# 2.net
KiCad netlist of a schematic drawn in Altium Designer
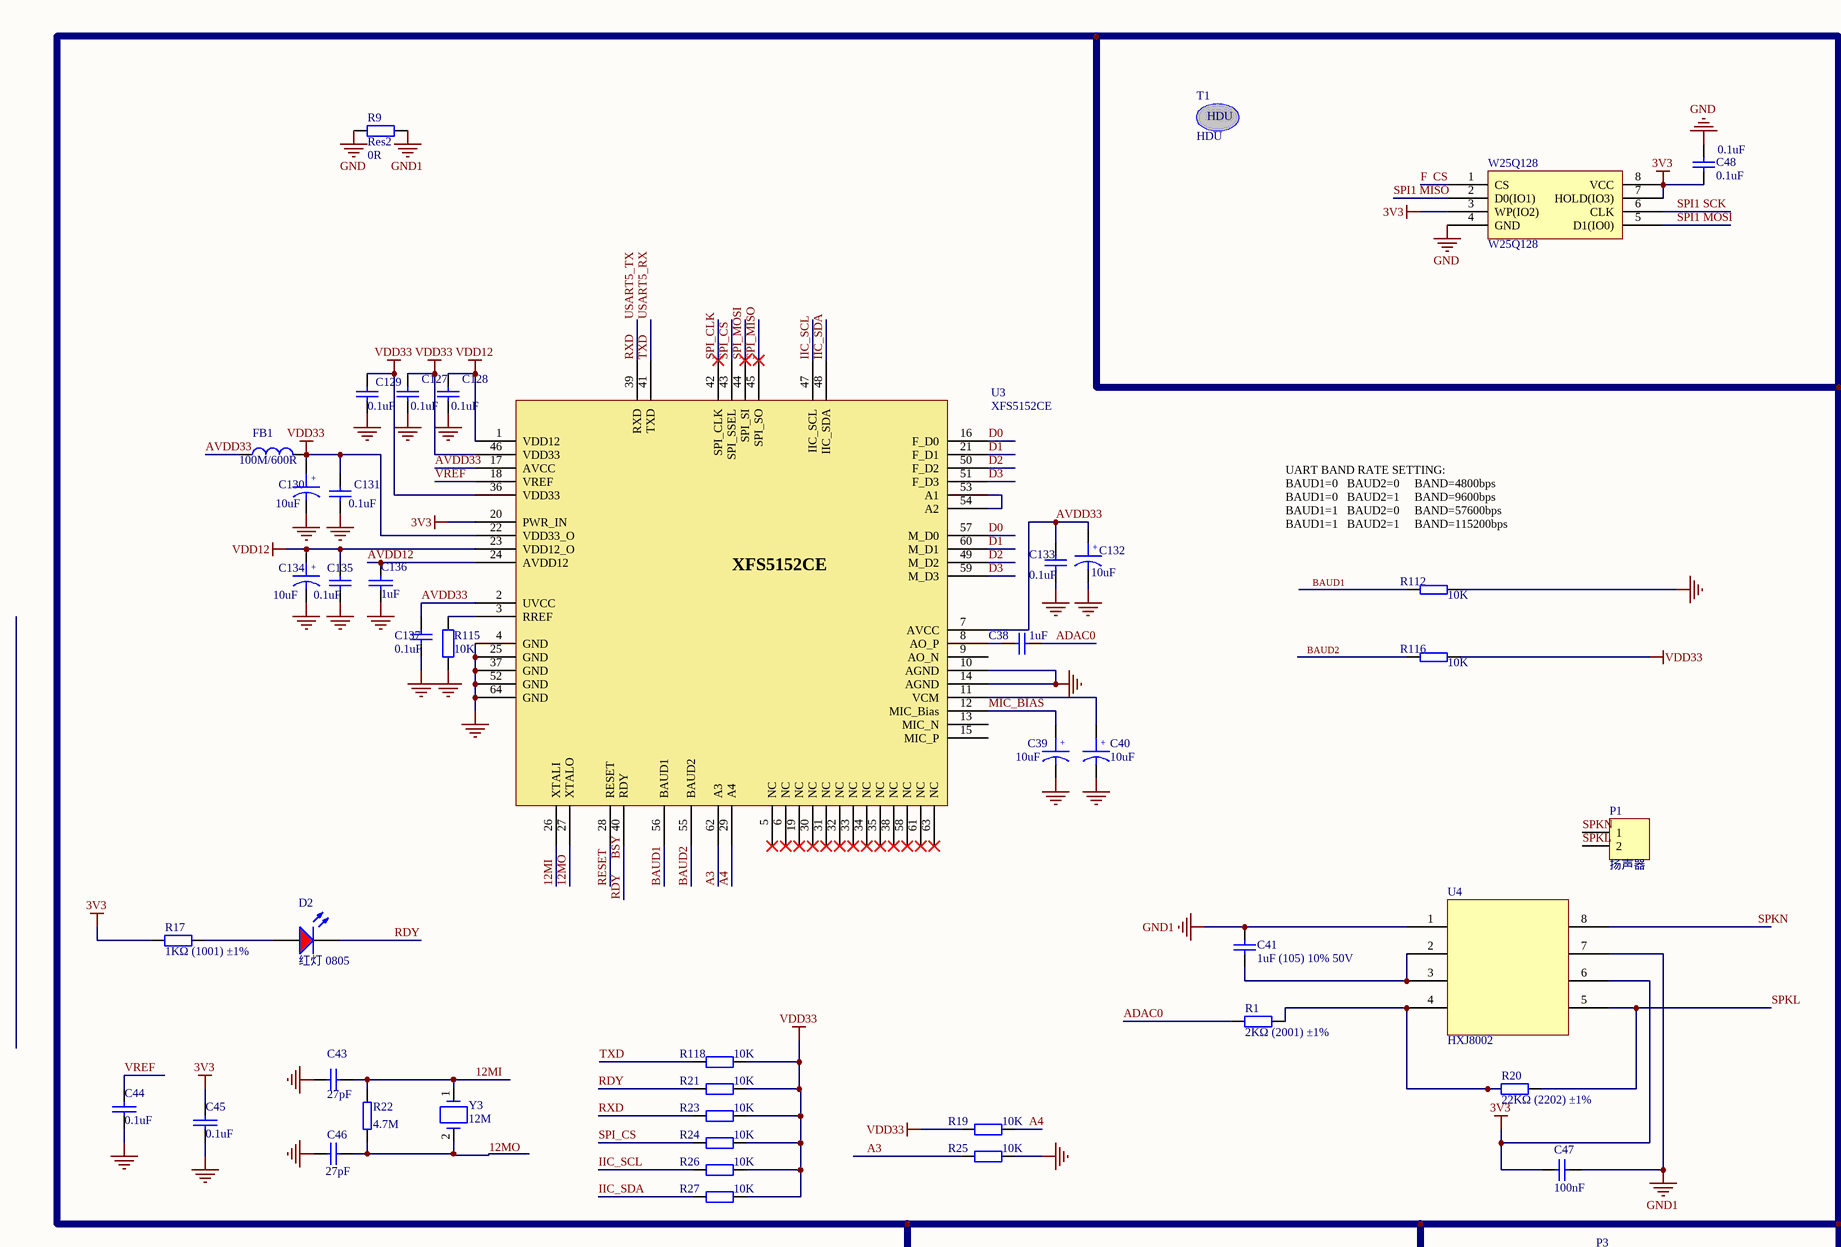
[diagram p0: 实验平台2.SchDoc, top left]
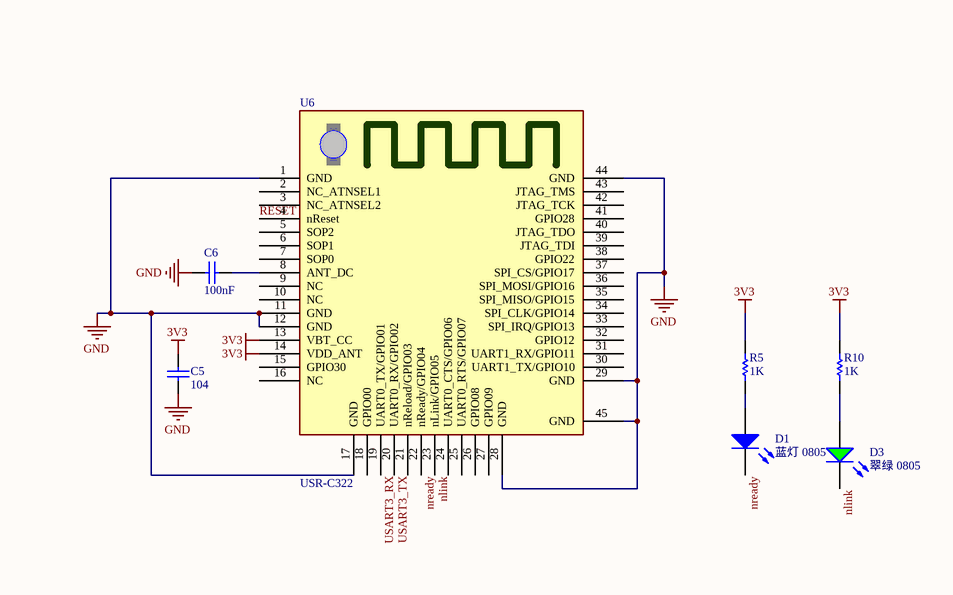
[diagram p1: 实验平台2.SchDoc, top right]
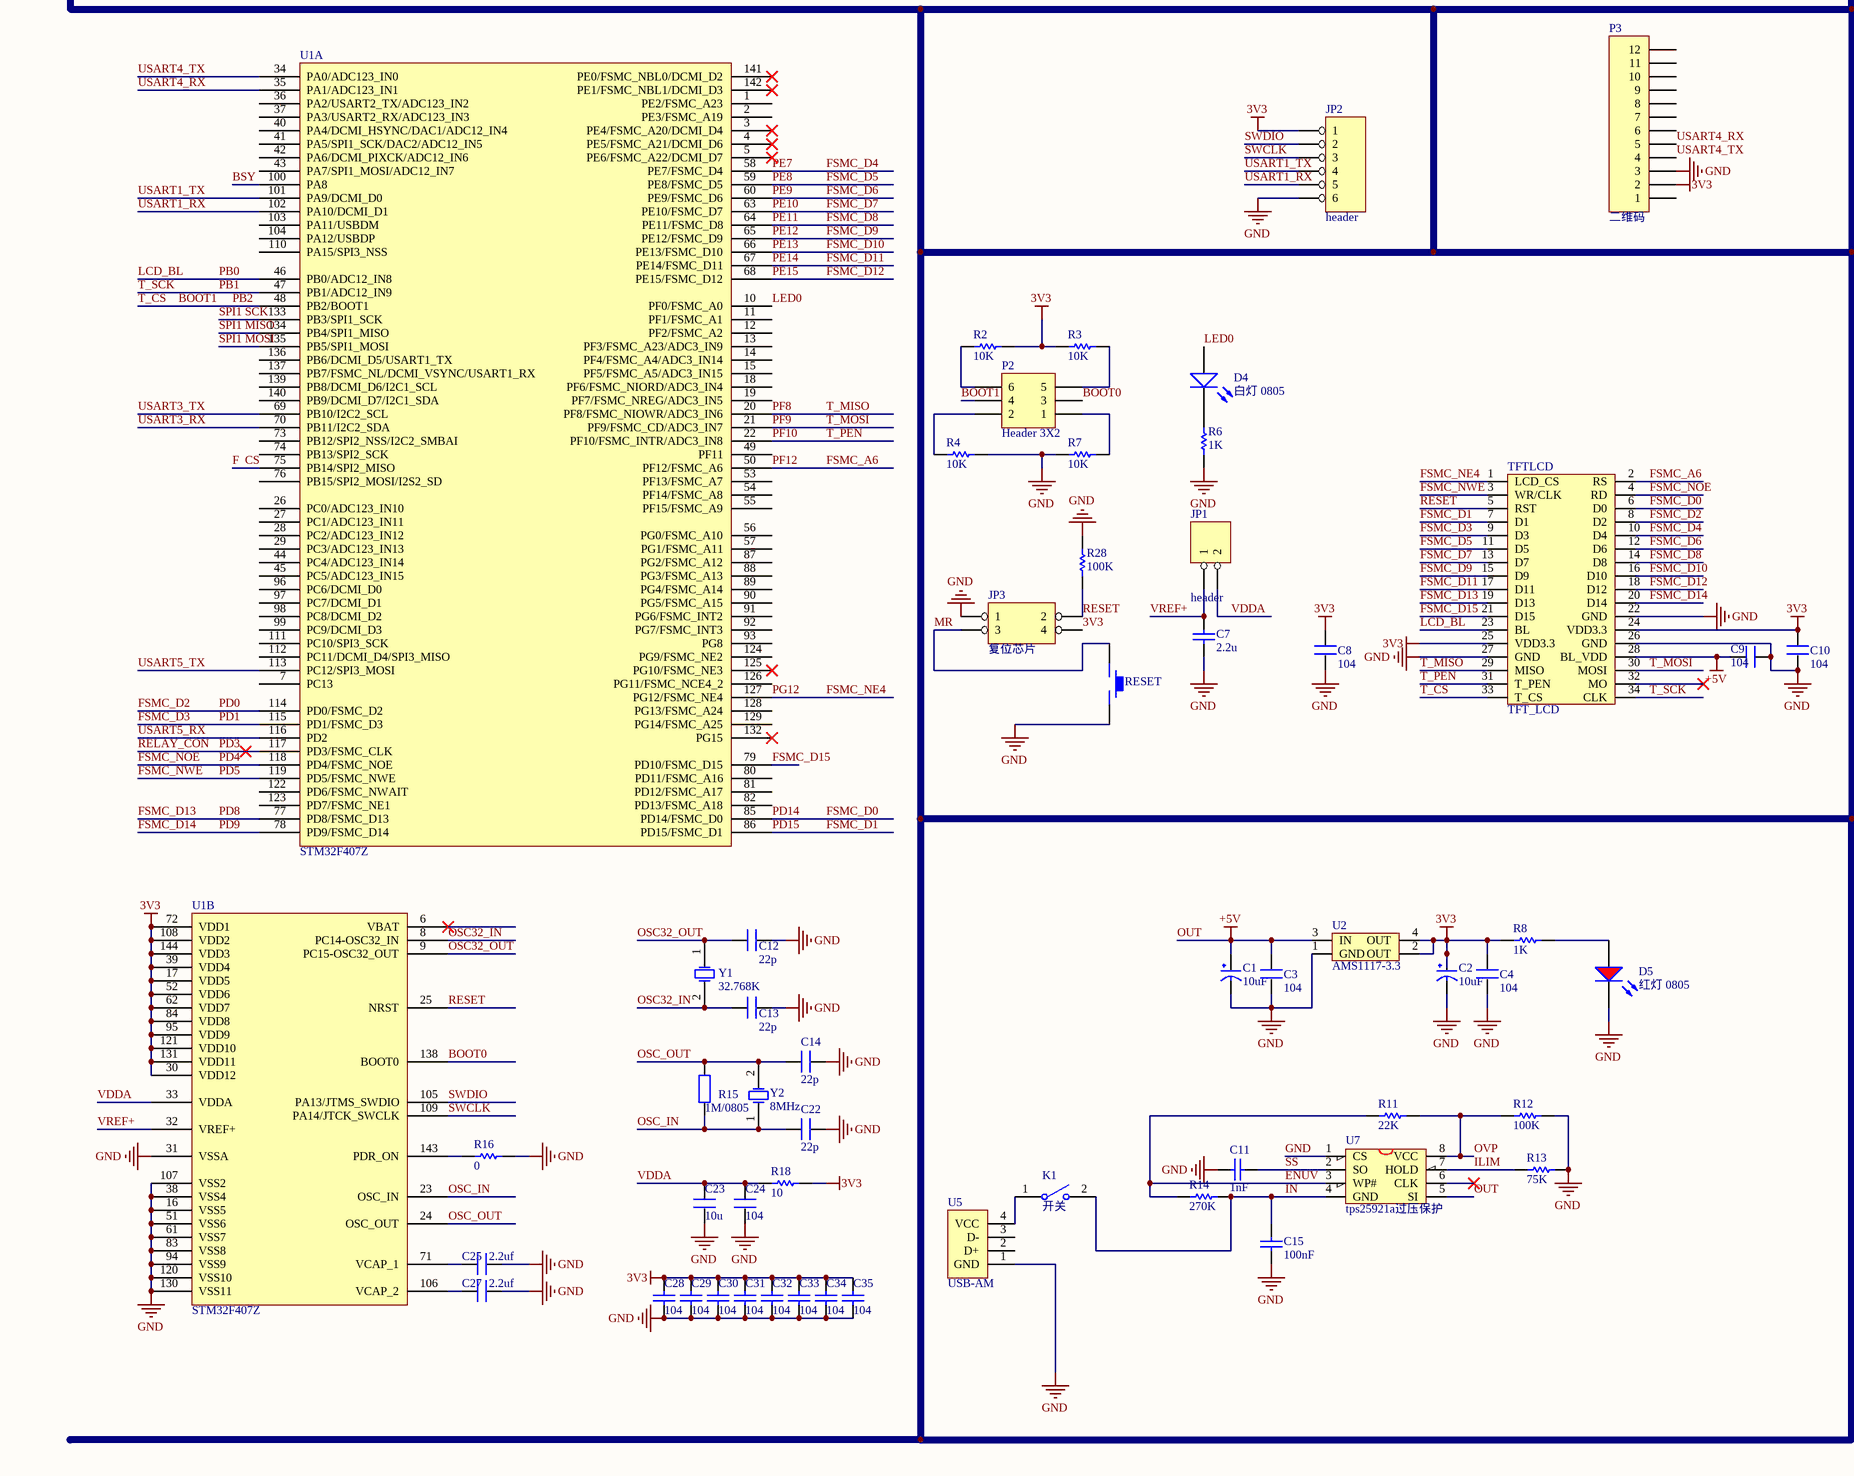
[diagram p2: 实验平台2.SchDoc, bottom left]

(export (version "E")
  (design (tool "Eeschema 10.0.6"))
  (components
    (comp (ref "C1")
      (value "10uF")
      (footprint "0603_c")
      (libsource (lib "Explorer STM32F407封装库") (part "CAP"))
    )
    (comp (ref "C2")
      (value "10uF")
      (footprint "0603_c")
      (libsource (lib "Explorer STM32F407封装库") (part "CAP"))
    )
    (comp (ref "C3")
      (value "104")
      (footprint "0603_c")
      (libsource (lib "Explorer STM32F407封装库") (part "C_3"))
    )
    (comp (ref "C4")
      (value "104")
      (footprint "0603_c")
      (libsource (lib "Explorer STM32F407封装库") (part "C_3"))
    )
    (comp (ref "C5")
      (value "104")
      (footprint "0603_c")
      (description "Capacitor")
      (fields (field (name "PUBLISHER") "Altium Limited"))
      (libsource (lib "My Footprint") (part "CAP"))
    )
    (comp (ref "C6")
      (value "100nF")
      (footprint "0603_C")
      (description "Capacitor")
      (fields (field (name "PUBLISHER") "Altium Limited"))
      (libsource (lib "My Footprint") (part "CAP"))
    )
    (comp (ref "C7")
      (value "2.2u")
      (footprint "0603_c")
      (description "Capacitor")
      (fields (field (name "PUBLISHER") "Altium Limited"))
      (libsource (lib "My Footprint") (part "CAP"))
    )
    (comp (ref "C8")
      (value "104")
      (footprint "0603_c")
      (libsource (lib "Explorer STM32F407封装库") (part "C_3"))
    )
    (comp (ref "C9")
      (value "104")
      (footprint "0603_c")
      (libsource (lib "Explorer STM32F407封装库") (part "C_3"))
    )
    (comp (ref "C10")
      (value "104")
      (footprint "0603_c")
      (libsource (lib "Explorer STM32F407封装库") (part "C_3"))
    )
    (comp (ref "C11")
      (value "1nF")
      (footprint "0603_C")
      (description "Capacitor")
      (fields (field (name "PUBLISHER") "Altium Limited"))
      (libsource (lib "My Footprint") (part "CAP"))
    )
    (comp (ref "C12")
      (value "22p")
      (footprint "0603_c")
      (libsource (lib "Explorer STM32F407封装库") (part "C_1"))
    )
    (comp (ref "C13")
      (value "22p")
      (footprint "0603_c")
      (libsource (lib "Explorer STM32F407封装库") (part "C_1"))
    )
    (comp (ref "C14")
      (value "22p")
      (footprint "0603_c")
      (libsource (lib "Explorer STM32F407封装库") (part "C_1"))
    )
    (comp (ref "C15")
      (value "100nF")
      (footprint "0603_C")
      (description "Capacitor")
      (fields (field (name "PUBLISHER") "Altium Limited"))
      (libsource (lib "My Footprint") (part "CAP"))
    )
    (comp (ref "C22")
      (value "22p")
      (footprint "0603_c")
      (libsource (lib "Explorer STM32F407封装库") (part "C_1"))
    )
    (comp (ref "C23")
      (value "10u")
      (footprint "0603_c")
      (libsource (lib "Explorer STM32F407封装库") (part "C_1"))
    )
    (comp (ref "C24")
      (value "104")
      (footprint "0603_c")
      (libsource (lib "Explorer STM32F407封装库") (part "C_1"))
    )
    (comp (ref "C25")
      (value "2.2uf")
      (footprint "0603_c")
      (libsource (lib "Explorer STM32F407封装库") (part "C_1"))
    )
    (comp (ref "C27")
      (value "2.2uf")
      (footprint "0603_c")
      (libsource (lib "Explorer STM32F407封装库") (part "C_1"))
    )
    (comp (ref "C28")
      (value "104")
      (footprint "0603_c")
      (description "Capacitor")
      (fields (field (name "PUBLISHER") "Altium Limited"))
      (libsource (lib "My Footprint") (part "CAP"))
    )
    (comp (ref "C29")
      (value "104")
      (footprint "0603_c")
      (description "Capacitor")
      (fields (field (name "PUBLISHER") "Altium Limited"))
      (libsource (lib "My Footprint") (part "CAP"))
    )
    (comp (ref "C30")
      (value "104")
      (footprint "0603_c")
      (description "Capacitor")
      (fields (field (name "PUBLISHER") "Altium Limited"))
      (libsource (lib "My Footprint") (part "CAP"))
    )
    (comp (ref "C31")
      (value "104")
      (footprint "0603_c")
      (description "Capacitor")
      (fields (field (name "PUBLISHER") "Altium Limited"))
      (libsource (lib "My Footprint") (part "CAP"))
    )
    (comp (ref "C32")
      (value "104")
      (footprint "0603_c")
      (description "Capacitor")
      (fields (field (name "PUBLISHER") "Altium Limited"))
      (libsource (lib "My Footprint") (part "CAP"))
    )
    (comp (ref "C33")
      (value "104")
      (footprint "0603_c")
      (description "Capacitor")
      (fields (field (name "PUBLISHER") "Altium Limited"))
      (libsource (lib "My Footprint") (part "CAP"))
    )
    (comp (ref "C34")
      (value "104")
      (footprint "0603_c")
      (description "Capacitor")
      (fields (field (name "PUBLISHER") "Altium Limited"))
      (libsource (lib "My Footprint") (part "CAP"))
    )
    (comp (ref "C35")
      (value "104")
      (footprint "0603_c")
      (description "Capacitor")
      (fields (field (name "PUBLISHER") "Altium Limited"))
      (libsource (lib "My Footprint") (part "CAP"))
    )
    (comp (ref "C38")
      (value "1uF")
      (footprint "C0603(1608)")
      (description "电容")
      (fields (field (name "PUBLISHER") "Altium Limited"))
      (libsource (lib "*") (part "Cap NP"))
    )
    (comp (ref "C39") (value "10uF") (footprint "C0603(1608)") (libsource (lib "*") (part "CAP POL")))
    (comp (ref "C40") (value "10uF") (footprint "C0603(1608)") (libsource (lib "*") (part "CAP POL")))
    (comp (ref "C41")
      (value "1uF (105) 10% 50V")
      (footprint "0603_C")
      (description "贴片电容")
      (libsource (lib "Miscellaneous Devices LC") (part "0603 1uF (105) 10% 50V"))
    )
    (comp (ref "C43")
      (value "27pF")
      (footprint "C0603(1608)")
      (description "电容")
      (fields (field (name "PUBLISHER") "Altium Limited"))
      (libsource (lib "*") (part "Cap NP"))
    )
    (comp (ref "C44")
      (value "0.1uF")
      (footprint "C0603(1608)")
      (description "Capacitor")
      (libsource (lib "*") (part "CAP"))
    )
    (comp (ref "C45")
      (value "0.1uF")
      (footprint "C0603(1608)")
      (description "Capacitor")
      (libsource (lib "*") (part "CAP"))
    )
    (comp (ref "C46")
      (value "27pF")
      (footprint "C0603(1608)")
      (description "电容")
      (fields (field (name "PUBLISHER") "Altium Limited"))
      (libsource (lib "*") (part "Cap NP"))
    )
    (comp (ref "C47")
      (value "100nF")
      (footprint "C-0603")
      (description "贴片电容")
      (libsource (lib "Miscellaneous Devices LC") (part "0805 10uF (106) 10% 25V"))
    )
    (comp (ref "C48")
      (value "0.1uF")
      (footprint "0603_C")
      (description "Capacitor")
      (fields (field (name "ALTIUM_VALUE") "0.1uF") (field (name "PUBLISHER") "Altium Limited"))
      (libsource (lib "Miscellaneous Devices") (part "Cap"))
    )
    (comp (ref "C127")
      (value "0.1uF")
      (footprint "C0603(1608)")
      (description "电容")
      (fields (field (name "PUBLISHER") "Altium Limited"))
      (libsource (lib "*") (part "Cap NP"))
    )
    (comp (ref "C128")
      (value "0.1uF")
      (footprint "C0603(1608)")
      (description "电容")
      (fields (field (name "PUBLISHER") "Altium Limited"))
      (libsource (lib "*") (part "Cap NP"))
    )
    (comp (ref "C129")
      (value "0.1uF")
      (footprint "C0603(1608)")
      (description "电容")
      (fields (field (name "PUBLISHER") "Altium Limited"))
      (libsource (lib "*") (part "Cap NP"))
    )
    (comp (ref "C130") (value "10uF") (footprint "C0603(1608)") (libsource (lib "*") (part "CAP POL")))
    (comp (ref "C131")
      (value "0.1uF")
      (footprint "C0603(1608)")
      (description "电容")
      (fields (field (name "PUBLISHER") "Altium Limited"))
      (libsource (lib "*") (part "Cap NP"))
    )
    (comp (ref "C132") (value "10uF") (footprint "C0603(1608)") (libsource (lib "*") (part "CAP POL")))
    (comp (ref "C133")
      (value "0.1uF")
      (footprint "C0603(1608)")
      (description "电容")
      (fields (field (name "PUBLISHER") "Altium Limited"))
      (libsource (lib "*") (part "Cap NP"))
    )
    (comp (ref "C134") (value "10uF") (footprint "C0603(1608)") (libsource (lib "*") (part "CAP POL")))
    (comp (ref "C135")
      (value "0.1uF")
      (footprint "C0603(1608)")
      (description "电容")
      (fields (field (name "PUBLISHER") "Altium Limited"))
      (libsource (lib "*") (part "Cap NP"))
    )
    (comp (ref "C136")
      (value "1uF")
      (footprint "C0603(1608)")
      (description "Capacitor")
      (libsource (lib "*") (part "CAP"))
    )
    (comp (ref "C137")
      (value "0.1uF")
      (footprint "C0603(1608)")
      (description "电容")
      (fields (field (name "PUBLISHER") "Altium Limited"))
      (libsource (lib "*") (part "Cap NP"))
    )
    (comp (ref "D1")
      (value "蓝灯 0805")
      (footprint "0805_LED_S1")
      (description "发光二极管")
      (libsource (lib "Miscellaneous Devices LC") (part "0805 蓝灯"))
    )
    (comp (ref "D2")
      (value "红灯 0805")
      (footprint "0805_LED_S1")
      (description "发光二极管")
      (libsource (lib "Miscellaneous Devices LC") (part "0805 红灯"))
    )
    (comp (ref "D3")
      (value "翠绿 0805")
      (footprint "0805_LED_S1")
      (description "发光二极管")
      (libsource (lib "Miscellaneous Devices LC") (part "0805 翠绿"))
    )
    (comp (ref "D4")
      (value "白灯 0805")
      (footprint "0805_LED_S1")
      (description "发光二极管")
      (libsource (lib "Miscellaneous Devices LC") (part "0805 白灯"))
    )
    (comp (ref "D5")
      (value "红灯 0805")
      (footprint "0805_LED_S1")
      (description "发光二极管")
      (libsource (lib "Miscellaneous Devices LC") (part "0805 红灯"))
    )
    (comp (ref "FB1")
      (value "100M/600R")
      (footprint "B0603")
      (description "磁珠")
      (fields (field (name "PUBLISHER") "Altium Limited"))
      (libsource (lib "*") (part "Fbead"))
    )
    (comp (ref "JP1")
      (value "header")
      (footprint "header2")
      (libsource (lib "My Footprint") (part "HEADER 2"))
    )
    (comp (ref "JP2")
      (value "header")
      (footprint "header6HA")
      (libsource (lib "My Footprint") (part "HEADER 6"))
    )
    (comp (ref "JP3")
      (value "复位芯片")
      (footprint "SOT-143_M")
      (libsource (lib "My Footprint") (part "HEADER 2X2"))
    )
    (comp (ref "K1") (value "开关") (footprint "kaiguan") (libsource (lib "单片机集成库") (part "开关")))
    (comp (ref "P1")
      (value "扬声器")
      (footprint "HDR1X2")
      (description "Header, 2-Pin")
      (fields (field (name "PUBLISHER") "Altium Limited"))
      (libsource (lib "Miscellaneous Connectors") (part "Header 2"))
    )
    (comp (ref "P2")
      (value "Header 3X2")
      (footprint "HDR2X3")
      (description "Header, 3-Pin, Dual row")
      (fields (field (name "PUBLISHER") "Altium Limited"))
      (libsource (lib "Miscellaneous Connectors") (part "Header 3X2"))
    )
    (comp (ref "P3")
      (value "二维码")
      (footprint "FH12A-12S-0.5sH")
      (description "Header, 12-Pin")
      (fields (field (name "PUBLISHER") "Altium Limited"))
      (libsource (lib "Miscellaneous Connectors") (part "Header 12"))
    )
    (comp (ref "R1")
      (value "2KΩ (2001) ±1%")
      (footprint "0603_R")
      (description "贴片电阻")
      (libsource (lib "Miscellaneous Devices LC") (part "0603 2KΩ (2001) 1%"))
    )
    (comp (ref "R2")
      (value "10K")
      (footprint "0603_r")
      (description "Resistor")
      (fields (field (name "PUBLISHER") "Altium Limited"))
      (libsource (lib "My Footprint") (part "RES"))
    )
    (comp (ref "R3")
      (value "10K")
      (footprint "0603_r")
      (description "Resistor")
      (fields (field (name "PUBLISHER") "Altium Limited"))
      (libsource (lib "My Footprint") (part "RES"))
    )
    (comp (ref "R4")
      (value "10K")
      (footprint "0603_r")
      (description "Resistor")
      (fields (field (name "PUBLISHER") "Altium Limited"))
      (libsource (lib "My Footprint") (part "RES"))
    )
    (comp (ref "R5")
      (value "1K")
      (footprint "0603_R")
      (description "Resistor")
      (fields (field (name "PUBLISHER") "Altium Limited"))
      (libsource (lib "My Footprint") (part "RES"))
    )
    (comp (ref "R6")
      (value "1K")
      (footprint "0603_r")
      (description "Resistor")
      (fields (field (name "PUBLISHER") "Altium Limited"))
      (libsource (lib "My Footprint") (part "RES"))
    )
    (comp (ref "R7")
      (value "10K")
      (footprint "0603_r")
      (description "Resistor")
      (fields (field (name "PUBLISHER") "Altium Limited"))
      (libsource (lib "My Footprint") (part "RES"))
    )
    (comp (ref "R8")
      (value "1K")
      (footprint "0603_R")
      (description "Resistor")
      (fields (field (name "PUBLISHER") "Altium Limited"))
      (libsource (lib "My Footprint") (part "RES"))
    )
    (comp (ref "R9")
      (value "Res2")
      (footprint "0805_r")
      (description "Resistor")
      (fields (field (name "ALTIUM_VALUE") "0R") (field (name "PUBLISHER") "Altium Limited"))
      (libsource (lib "Miscellaneous Devices") (part "Res2"))
    )
    (comp (ref "R10")
      (value "1K")
      (footprint "0603_R")
      (description "Resistor")
      (fields (field (name "PUBLISHER") "Altium Limited"))
      (libsource (lib "My Footprint") (part "RES"))
    )
    (comp (ref "R11")
      (value "22K")
      (footprint "0603_R")
      (description "Resistor")
      (fields (field (name "PUBLISHER") "Altium Limited"))
      (libsource (lib "My Footprint") (part "RES"))
    )
    (comp (ref "R12")
      (value "100K")
      (footprint "0603_R")
      (description "Resistor")
      (fields (field (name "PUBLISHER") "Altium Limited"))
      (libsource (lib "My Footprint") (part "RES"))
    )
    (comp (ref "R13")
      (value "75K")
      (footprint "0603_R")
      (description "Resistor")
      (fields (field (name "PUBLISHER") "Altium Limited"))
      (libsource (lib "My Footprint") (part "RES"))
    )
    (comp (ref "R14")
      (value "270K")
      (footprint "0603_R")
      (description "Resistor")
      (fields (field (name "PUBLISHER") "Altium Limited"))
      (libsource (lib "My Footprint") (part "RES"))
    )
    (comp (ref "R15")
      (value "1M/0805")
      (footprint "0603_r")
      (description "Resistor")
      (fields (field (name "PUBLISHER") "Altium Limited"))
      (libsource (lib "STM32F407VET6mini最小系统-原理图库") (part "Res2"))
    )
    (comp (ref "R16")
      (value "0")
      (footprint "0603_r")
      (description "Resistor")
      (fields (field (name "PUBLISHER") "Altium Limited"))
      (libsource (lib "My Footprint") (part "RES"))
    )
    (comp (ref "R17")
      (value "1KΩ (1001) ±1%")
      (footprint "0603_R")
      (description "贴片电阻")
      (libsource (lib "Miscellaneous Devices LC") (part "0805 1KΩ (1001) 1%"))
    )
    (comp (ref "R18")
      (value "10")
      (footprint "0603_r")
      (description "Resistor")
      (fields (field (name "PUBLISHER") "Altium Limited"))
      (libsource (lib "My Footprint") (part "RES"))
    )
    (comp (ref "R19")
      (value "10K")
      (footprint "R0603")
      (description "Resistor")
      (fields (field (name "PUBLISHER") "Altium Limited"))
      (libsource (lib "*") (part "Res2"))
    )
    (comp (ref "R20")
      (value "22KΩ (2202) ±1%")
      (footprint "0603_R")
      (description "贴片电阻")
      (libsource (lib "Miscellaneous Devices LC") (part "0805 22KΩ (2202) 1%"))
    )
    (comp (ref "R21")
      (value "10K")
      (footprint "R0603")
      (description "Resistor")
      (fields (field (name "PUBLISHER") "Altium Limited"))
      (libsource (lib "*") (part "Res2"))
    )
    (comp (ref "R22")
      (value "4.7M")
      (footprint "R0603")
      (description "电阻")
      (libsource (lib "*") (part "RES2"))
    )
    (comp (ref "R23")
      (value "10K")
      (footprint "R0603")
      (description "Resistor")
      (fields (field (name "PUBLISHER") "Altium Limited"))
      (libsource (lib "*") (part "Res2"))
    )
    (comp (ref "R24")
      (value "10K")
      (footprint "R0603")
      (description "Resistor")
      (fields (field (name "PUBLISHER") "Altium Limited"))
      (libsource (lib "*") (part "Res2"))
    )
    (comp (ref "R25")
      (value "10K")
      (footprint "R0603")
      (description "Resistor")
      (fields (field (name "PUBLISHER") "Altium Limited"))
      (libsource (lib "*") (part "Res2"))
    )
    (comp (ref "R26")
      (value "10K")
      (footprint "R0603")
      (description "Resistor")
      (fields (field (name "PUBLISHER") "Altium Limited"))
      (libsource (lib "*") (part "Res2"))
    )
    (comp (ref "R27")
      (value "10K")
      (footprint "R0603")
      (description "Resistor")
      (fields (field (name "PUBLISHER") "Altium Limited"))
      (libsource (lib "*") (part "Res2"))
    )
    (comp (ref "R28")
      (value "100K")
      (footprint "0603_R")
      (description "Resistor")
      (fields (field (name "PUBLISHER") "Altium Limited"))
      (libsource (lib "My Footprint") (part "RES"))
    )
    (comp (ref "R112")
      (value "10K")
      (footprint "R0603")
      (description "电阻")
      (libsource (lib "*") (part "RES2"))
    )
    (comp (ref "R115")
      (value "10K")
      (footprint "R0603")
      (description "Resistor")
      (fields (field (name "PUBLISHER") "Altium Limited"))
      (libsource (lib "") (part "Res2_1"))
    )
    (comp (ref "R116")
      (value "10K")
      (footprint "R0603")
      (description "电阻")
      (libsource (lib "*") (part "RES2"))
    )
    (comp (ref "R118")
      (value "10K")
      (footprint "R0603")
      (description "Resistor")
      (fields (field (name "PUBLISHER") "Altium Limited"))
      (libsource (lib "*") (part "Res2"))
    )
    (comp (ref "RESET")
      (value "KEY_M")
      (footprint "KEY_M")
      (libsource (lib "Explorer STM32F407封装库") (part "KEY_M"))
    )
    (comp (ref "T1") (value "HDU") (footprint "HDU") (libsource (lib "My Footprint") (part "HDU")))
    (comp (ref "TFTLCD")
      (value "TFT_LCD")
      (footprint "HDR2X17")
      (libsource (lib "Explorer STM32F407封装库") (part "TFT_LCD"))
    )
    (comp (ref "U1")
      (value "STM32F407Z")
      (footprint "LQFP144")
      (description "STM32单片机144引脚")
      (libsource (lib "Fszhang") (part "STM32F407Z"))
    )
    (comp (ref "U2")
      (value "AMS1117-3.3")
      (footprint "AMS1117")
      (libsource (lib "Explorer STM32F407封装库") (part "AMS1117"))
    )
    (comp (ref "U3")
      (value "XFS5152CE")
      (footprint "LQFP-64_10x10x05P")
      (libsource (lib "*") (part "XFS5152-2"))
    )
    (comp (ref "U4") (value "HXJ8002") (footprint "SOIC-8") (libsource (lib "My Footprint") (part "LM358")))
    (comp (ref "U5")
      (value "USB-AM")
      (footprint "USB_AM")
      (description "Data line")
      (libsource (lib "My Footprint") (part "USB-AM"))
    )
    (comp (ref "U6")
      (value "USR-C322")
      (footprint "USR-C322-PCB")
      (libsource (lib "USR-C322") (part "USR-C322"))
    )
    (comp (ref "U7")
      (value "tps25921a过压保护")
      (footprint "SOIC-8")
      (description "W25X16;SST25VF016;MX25L1605")
      (libsource (lib "MiniSTM32 V3.0封装库") (part "W25X16"))
    )
    (comp (ref "W25Q128") (value "W25Q128") (footprint "SO-8N") (libsource (lib "TPS7333") (part "W25Q128")))
    (comp (ref "Y1")
      (value "32.768K")
      (footprint "XTAL_32")
      (description "Crystal Oscillator")
      (fields (field (name "PUBLISHER") "Altium Limited"))
      (libsource (lib "Explorer STM32F407封装库") (part "XTAL_1"))
    )
    (comp (ref "Y2")
      (value "8MHz")
      (footprint "XTAL_2")
      (description "Crystal Oscillator")
      (fields (field (name "PUBLISHER") "Altium Limited"))
      (libsource (lib "STM32F407VET6mini最小系统-原理图库") (part "XTAL"))
    )
    (comp (ref "Y3")
      (value "12M")
      (footprint "XTAL_2")
      (description "晶振")
      (libsource (lib "*") (part "XTAL1"))
    )
  )
  (nets
    (net (code "1") (name "+5V") (class "Default")
      (node (ref "C1") (pin "1") (pinfunction "VCC_1") (pintype "passive"))
      (node (ref "C3") (pin "2") (pintype "passive"))
      (node (ref "C9") (pin "1") (pintype "passive"))
      (node (ref "TFTLCD") (pin "28") (pinfunction "BL_VDD_28") (pintype "passive"))
      (node (ref "U2") (pin "3") (pinfunction "IN_3") (pintype "passive"))
      (node (ref "U7") (pin "5") (pinfunction "SI_5") (pintype "passive"))
    )
    (net (code "2") (name "/12MI") (class "Default")
      (node (ref "C43") (pin "2") (pinfunction "2_2") (pintype "passive"))
      (node (ref "R22") (pin "1") (pintype "passive"))
      (node (ref "U3") (pin "26") (pinfunction "XTALI_26") (pintype "passive"))
      (node (ref "Y3") (pin "1") (pinfunction "1_1") (pintype "passive"))
    )
    (net (code "3") (name "/12MO") (class "Default")
      (node (ref "C46") (pin "2") (pinfunction "2_2") (pintype "passive"))
      (node (ref "R22") (pin "2") (pintype "passive"))
      (node (ref "U3") (pin "27") (pinfunction "XTALO_27") (pintype "passive"))
      (node (ref "Y3") (pin "2") (pinfunction "2_2") (pintype "passive"))
    )
    (net (code "4") (name "/A3") (class "Default")
      (node (ref "R25") (pin "2") (pinfunction "2_2") (pintype "passive"))
      (node (ref "U3") (pin "62") (pinfunction "A3_62") (pintype "passive"))
    )
    (net (code "5") (name "/A4") (class "Default")
      (node (ref "R19") (pin "1") (pinfunction "1_1") (pintype "passive"))
      (node (ref "U3") (pin "29") (pinfunction "A4_29") (pintype "passive"))
    )
    (net (code "6") (name "/ADAC0") (class "Default")
      (node (ref "C38") (pin "1") (pinfunction "1_1") (pintype "passive"))
      (node (ref "R1") (pin "1") (pinfunction "1_1") (pintype "passive"))
    )
    (net (code "7") (name "/AVDD12") (class "Default")
      (node (ref "C136") (pin "1") (pinfunction "1_1") (pintype "passive"))
      (node (ref "U3") (pin "24") (pinfunction "AVDD12_24") (pintype "passive"))
    )
    (net (code "8") (name "/AVDD33") (class "Default")
      (node (ref "C132") (pin "1") (pinfunction "1_1") (pintype "passive"))
      (node (ref "C133") (pin "2") (pinfunction "2_2") (pintype "passive"))
      (node (ref "C137") (pin "2") (pinfunction "2_2") (pintype "passive"))
      (node (ref "FB1") (pin "1") (pinfunction "1_1") (pintype "passive"))
      (node (ref "U3") (pin "17") (pinfunction "AVCC_17") (pintype "passive"))
      (node (ref "U3") (pin "2") (pinfunction "UVCC_2") (pintype "passive"))
      (node (ref "U3") (pin "7") (pinfunction "AVCC_7") (pintype "passive"))
    )
    (net (code "9") (name "/BAUD1") (class "Default")
      (node (ref "R112") (pin "2") (pintype "passive"))
      (node (ref "U3") (pin "56") (pinfunction "BAUD1_56") (pintype "passive"))
    )
    (net (code "10") (name "/BAUD2") (class "Default")
      (node (ref "R116") (pin "1") (pintype "passive"))
      (node (ref "U3") (pin "55") (pinfunction "BAUD2_55") (pintype "passive"))
    )
    (net (code "11") (name "/BOOT0") (class "Default")
      (node (ref "P2") (pin "3") (pinfunction "3_3") (pintype "passive"))
      (node (ref "U1") (pin "138") (pinfunction "BOOT0_138") (pintype "passive"))
    )
    (net (code "12") (name "/BOOT1") (class "Default")
      (node (ref "P2") (pin "4") (pinfunction "4_4") (pintype "passive"))
      (node (ref "TFTLCD") (pin "33") (pinfunction "T_CS_33") (pintype "passive"))
      (node (ref "U1") (pin "48") (pinfunction "PB2/BOOT1_48") (pintype "passive"))
    )
    (net (code "13") (name "/BSY") (class "Default")
      (node (ref "D2") (pin "K") (pinfunction "K_K") (pintype "passive"))
      (node (ref "R21") (pin "2") (pinfunction "2_2") (pintype "passive"))
      (node (ref "U1") (pin "100") (pinfunction "PA8_100") (pintype "passive"))
      (node (ref "U3") (pin "40") (pinfunction "RDY_40") (pintype "passive"))
    )
    (net (code "14") (name "/D0") (class "Default")
      (node (ref "U3") (pin "16") (pinfunction "F_D0_16") (pintype "passive"))
      (node (ref "U3") (pin "57") (pinfunction "M_D0_57") (pintype "passive"))
    )
    (net (code "15") (name "/D1") (class "Default")
      (node (ref "U3") (pin "21") (pinfunction "F_D1_21") (pintype "passive"))
      (node (ref "U3") (pin "60") (pinfunction "M_D1_60") (pintype "passive"))
    )
    (net (code "16") (name "/D2") (class "Default")
      (node (ref "U3") (pin "49") (pinfunction "M_D2_49") (pintype "passive"))
      (node (ref "U3") (pin "50") (pinfunction "F_D2_50") (pintype "passive"))
    )
    (net (code "17") (name "/D3") (class "Default")
      (node (ref "U3") (pin "51") (pinfunction "F_D3_51") (pintype "passive"))
      (node (ref "U3") (pin "59") (pinfunction "M_D3_59") (pintype "passive"))
    )
    (net (code "18") (name "/ENUV") (class "Default")
      (node (ref "R11") (pin "1") (pinfunction "1_1") (pintype "passive"))
      (node (ref "R14") (pin "1") (pinfunction "1_1") (pintype "passive"))
      (node (ref "U7") (pin "3") (pinfunction "WP#_3") (pintype "passive"))
    )
    (net (code "19") (name "/F  CS") (class "Default")
      (node (ref "U1") (pin "75") (pinfunction "PB14/SPI2_MISO_75") (pintype "passive"))
      (node (ref "W25Q128") (pin "1") (pinfunction "CS_1") (pintype "passive"))
    )
    (net (code "20") (name "/FSMC_A6") (class "Default")
      (node (ref "TFTLCD") (pin "2") (pinfunction "RS_2") (pintype "passive"))
      (node (ref "U1") (pin "50") (pinfunction "PF12/FSMC_A6_50") (pintype "passive"))
    )
    (net (code "21") (name "/FSMC_D0") (class "Default")
      (node (ref "TFTLCD") (pin "6") (pinfunction "D0_6") (pintype "passive"))
      (node (ref "U1") (pin "85") (pinfunction "PD14/FSMC_D0_85") (pintype "passive"))
    )
    (net (code "22") (name "/FSMC_D1") (class "Default")
      (node (ref "TFTLCD") (pin "7") (pinfunction "D1_7") (pintype "passive"))
      (node (ref "U1") (pin "86") (pinfunction "PD15/FSMC_D1_86") (pintype "passive"))
    )
    (net (code "23") (name "/FSMC_D2") (class "Default")
      (node (ref "TFTLCD") (pin "8") (pinfunction "D2_8") (pintype "passive"))
      (node (ref "U1") (pin "114") (pinfunction "PD0/FSMC_D2_114") (pintype "passive"))
    )
    (net (code "24") (name "/FSMC_D3") (class "Default")
      (node (ref "TFTLCD") (pin "9") (pinfunction "D3_9") (pintype "passive"))
      (node (ref "U1") (pin "115") (pinfunction "PD1/FSMC_D3_115") (pintype "passive"))
    )
    (net (code "25") (name "/FSMC_D4") (class "Default")
      (node (ref "TFTLCD") (pin "10") (pinfunction "D4_10") (pintype "passive"))
      (node (ref "U1") (pin "58") (pinfunction "PE7/FSMC_D4_58") (pintype "passive"))
    )
    (net (code "26") (name "/FSMC_D5") (class "Default")
      (node (ref "TFTLCD") (pin "11") (pinfunction "D5_11") (pintype "passive"))
      (node (ref "U1") (pin "59") (pinfunction "PE8/FSMC_D5_59") (pintype "passive"))
    )
    (net (code "27") (name "/FSMC_D6") (class "Default")
      (node (ref "TFTLCD") (pin "12") (pinfunction "D6_12") (pintype "passive"))
      (node (ref "U1") (pin "60") (pinfunction "PE9/FSMC_D6_60") (pintype "passive"))
    )
    (net (code "28") (name "/FSMC_D7") (class "Default")
      (node (ref "TFTLCD") (pin "13") (pinfunction "D7_13") (pintype "passive"))
      (node (ref "U1") (pin "63") (pinfunction "PE10/FSMC_D7_63") (pintype "passive"))
    )
    (net (code "29") (name "/FSMC_D8") (class "Default")
      (node (ref "TFTLCD") (pin "14") (pinfunction "D8_14") (pintype "passive"))
      (node (ref "U1") (pin "64") (pinfunction "PE11/FSMC_D8_64") (pintype "passive"))
    )
    (net (code "30") (name "/FSMC_D9") (class "Default")
      (node (ref "TFTLCD") (pin "15") (pinfunction "D9_15") (pintype "passive"))
      (node (ref "U1") (pin "65") (pinfunction "PE12/FSMC_D9_65") (pintype "passive"))
    )
    (net (code "31") (name "/FSMC_D10") (class "Default")
      (node (ref "TFTLCD") (pin "16") (pinfunction "D10_16") (pintype "passive"))
      (node (ref "U1") (pin "66") (pinfunction "PE13/FSMC_D10_66") (pintype "passive"))
    )
    (net (code "32") (name "/FSMC_D11") (class "Default")
      (node (ref "TFTLCD") (pin "17") (pinfunction "D11_17") (pintype "passive"))
      (node (ref "U1") (pin "67") (pinfunction "PE14/FSMC_D11_67") (pintype "passive"))
    )
    (net (code "33") (name "/FSMC_D12") (class "Default")
      (node (ref "TFTLCD") (pin "18") (pinfunction "D12_18") (pintype "passive"))
      (node (ref "U1") (pin "68") (pinfunction "PE15/FSMC_D12_68") (pintype "passive"))
    )
    (net (code "34") (name "/FSMC_D13") (class "Default")
      (node (ref "TFTLCD") (pin "19") (pinfunction "D13_19") (pintype "passive"))
      (node (ref "U1") (pin "77") (pinfunction "PD8/FSMC_D13_77") (pintype "passive"))
    )
    (net (code "35") (name "/FSMC_D14") (class "Default")
      (node (ref "TFTLCD") (pin "20") (pinfunction "D14_20") (pintype "passive"))
      (node (ref "U1") (pin "78") (pinfunction "PD9/FSMC_D14_78") (pintype "passive"))
    )
    (net (code "36") (name "/FSMC_D15") (class "Default")
      (node (ref "TFTLCD") (pin "21") (pinfunction "D15_21") (pintype "passive"))
      (node (ref "U1") (pin "79") (pinfunction "PD10/FSMC_D15_79") (pintype "passive"))
    )
    (net (code "37") (name "/FSMC_NE4") (class "Default")
      (node (ref "TFTLCD") (pin "1") (pinfunction "LCD_CS_1") (pintype "passive"))
      (node (ref "U1") (pin "127") (pinfunction "PG12/FSMC_NE4_127") (pintype "passive"))
    )
    (net (code "38") (name "/FSMC_NOE") (class "Default")
      (node (ref "TFTLCD") (pin "4") (pinfunction "RD_4") (pintype "passive"))
      (node (ref "U1") (pin "118") (pinfunction "PD4/FSMC_NOE_118") (pintype "passive"))
    )
    (net (code "39") (name "/FSMC_NWE") (class "Default")
      (node (ref "TFTLCD") (pin "3") (pinfunction "WR/CLK_3") (pintype "passive"))
      (node (ref "U1") (pin "119") (pinfunction "PD5/FSMC_NWE_119") (pintype "passive"))
    )
    (net (code "40") (name "/IIC_SCL") (class "Default")
      (node (ref "R26") (pin "2") (pinfunction "2_2") (pintype "passive"))
      (node (ref "U3") (pin "47") (pinfunction "IIC_SCL_47") (pintype "passive"))
    )
    (net (code "41") (name "/IIC_SDA") (class "Default")
      (node (ref "R27") (pin "2") (pinfunction "2_2") (pintype "passive"))
      (node (ref "U3") (pin "48") (pinfunction "IIC_SDA_48") (pintype "passive"))
    )
    (net (code "42") (name "/ILIM") (class "Default")
      (node (ref "R13") (pin "1") (pinfunction "1_1") (pintype "passive"))
      (node (ref "U7") (pin "7") (pinfunction "HOLD_7") (pintype "passive"))
    )
    (net (code "43") (name "/IN") (class "Default")
      (node (ref "C15") (pin "2") (pinfunction "2_2") (pintype "passive"))
      (node (ref "K1") (pin "2") (pinfunction "NO_2") (pintype "passive"))
      (node (ref "R14") (pin "2") (pinfunction "2_2") (pintype "passive"))
      (node (ref "U7") (pin "4") (pinfunction "GND_4") (pintype "passive"))
    )
    (net (code "44") (name "/LCD_BL") (class "Default")
      (node (ref "TFTLCD") (pin "23") (pinfunction "BL_23") (pintype "passive"))
      (node (ref "U1") (pin "46") (pinfunction "PB0/ADC12_IN8_46") (pintype "passive"))
    )
    (net (code "45") (name "/LED0") (class "Default")
      (node (ref "D4") (pin "A") (pinfunction "A_A") (pintype "passive"))
      (node (ref "U1") (pin "10") (pinfunction "PF0/FSMC_A0_10") (pintype "passive"))
    )
    (net (code "46") (name "/MIC_BIAS") (class "Default")
      (node (ref "C39") (pin "1") (pinfunction "1_1") (pintype "passive"))
      (node (ref "U3") (pin "12") (pinfunction "MIC_Bias_12") (pintype "passive"))
    )
    (net (code "47") (name "/MR") (class "Default")
      (node (ref "JP3") (pin "3") (pinfunction "3_3") (pintype "passive"))
      (node (ref "RESET") (pin "1") (pinfunction "1_1") (pintype "passive"))
    )
    (net (code "48") (name "/OSC32_IN") (class "Default")
      (node (ref "C13") (pin "2") (pintype "passive"))
      (node (ref "U1") (pin "8") (pinfunction "PC14-OSC32_IN_8") (pintype "passive"))
      (node (ref "Y1") (pin "2") (pinfunction "OSC2_2") (pintype "passive"))
    )
    (net (code "49") (name "/OSC32_OUT") (class "Default")
      (node (ref "C12") (pin "2") (pintype "passive"))
      (node (ref "U1") (pin "9") (pinfunction "PC15-OSC32_OUT_9") (pintype "passive"))
      (node (ref "Y1") (pin "1") (pinfunction "OSC1_1") (pintype "passive"))
    )
    (net (code "50") (name "/OSC_IN") (class "Default")
      (node (ref "C22") (pin "1") (pintype "passive"))
      (node (ref "R15") (pin "1") (pinfunction "1_1") (pintype "passive"))
      (node (ref "U1") (pin "23") (pinfunction "OSC_IN_23") (pintype "passive"))
      (node (ref "Y2") (pin "1") (pinfunction "OSC1_1") (pintype "passive"))
    )
    (net (code "51") (name "/OSC_OUT") (class "Default")
      (node (ref "C14") (pin "1") (pintype "passive"))
      (node (ref "R15") (pin "2") (pinfunction "2_2") (pintype "passive"))
      (node (ref "U1") (pin "24") (pinfunction "OSC_OUT_24") (pintype "passive"))
      (node (ref "Y2") (pin "2") (pinfunction "OSC2_2") (pintype "passive"))
    )
    (net (code "52") (name "/OVP") (class "Default")
      (node (ref "R11") (pin "2") (pinfunction "2_2") (pintype "passive"))
      (node (ref "R12") (pin "1") (pinfunction "1_1") (pintype "passive"))
      (node (ref "U7") (pin "8") (pinfunction "VCC_8") (pintype "passive"))
    )
    (net (code "53") (name "/PB1") (class "Default")
      (node (ref "TFTLCD") (pin "34") (pinfunction "CLK_34") (pintype "passive"))
      (node (ref "U1") (pin "47") (pinfunction "PB1/ADC12_IN9_47") (pintype "passive"))
    )
    (net (code "54") (name "/PD3") (class "Default")
      (node (ref "U1") (pin "117") (pinfunction "PD3/FSMC_CLK_117") (pintype "passive"))
    )
    (net (code "55") (name "/PF8") (class "Default")
      (node (ref "TFTLCD") (pin "29") (pinfunction "MISO_29") (pintype "passive"))
      (node (ref "U1") (pin "20") (pinfunction "PF8/FSMC_NIOWR/ADC3_IN6_20") (pintype "passive"))
    )
    (net (code "56") (name "/PF9") (class "Default")
      (node (ref "TFTLCD") (pin "30") (pinfunction "MOSI_30") (pintype "passive"))
      (node (ref "U1") (pin "21") (pinfunction "PF9/FSMC_CD/ADC3_IN7_21") (pintype "passive"))
    )
    (net (code "57") (name "/PF10") (class "Default")
      (node (ref "TFTLCD") (pin "31") (pinfunction "T_PEN_31") (pintype "passive"))
      (node (ref "U1") (pin "22") (pinfunction "PF10/FSMC_INTR/ADC3_IN8_22") (pintype "passive"))
    )
    (net (code "58") (name "/RESET") (class "Default")
      (node (ref "JP3") (pin "2") (pinfunction "2_2") (pintype "passive"))
      (node (ref "R28") (pin "1") (pinfunction "1_1") (pintype "passive"))
      (node (ref "TFTLCD") (pin "5") (pinfunction "RST_5") (pintype "passive"))
      (node (ref "U1") (pin "25") (pinfunction "NRST_25") (pintype "passive"))
      (node (ref "U3") (pin "28") (pinfunction "RESET_28") (pintype "passive"))
      (node (ref "U6") (pin "4") (pinfunction "nReset_4") (pintype "passive"))
    )
    (net (code "59") (name "/RXD") (class "Default")
      (node (ref "R23") (pin "2") (pinfunction "2_2") (pintype "passive"))
      (node (ref "U1") (pin "113") (pinfunction "PC12/SPI3_MOSI_113") (pintype "passive"))
      (node (ref "U3") (pin "39") (pinfunction "RXD_39") (pintype "passive"))
    )
    (net (code "60") (name "/SPI1 MISO") (class "Default")
      (node (ref "U1") (pin "134") (pinfunction "PB4/SPI1_MISO_134") (pintype "passive"))
      (node (ref "W25Q128") (pin "2") (pinfunction "D0(IO1)_2") (pintype "passive"))
    )
    (net (code "61") (name "/SPI1 MOSI") (class "Default")
      (node (ref "U1") (pin "135") (pinfunction "PB5/SPI1_MOSI_135") (pintype "passive"))
      (node (ref "W25Q128") (pin "5") (pinfunction "D1(IO0)_5") (pintype "passive"))
    )
    (net (code "62") (name "/SPI1 SCK") (class "Default")
      (node (ref "U1") (pin "133") (pinfunction "PB3/SPI1_SCK_133") (pintype "passive"))
      (node (ref "W25Q128") (pin "6") (pinfunction "CLK_6") (pintype "passive"))
    )
    (net (code "63") (name "/SPI_CLK") (class "Default")
      (node (ref "U3") (pin "42") (pinfunction "SPI_CLK_42") (pintype "passive+no_connect"))
    )
    (net (code "64") (name "/SPI_CS") (class "Default")
      (node (ref "R24") (pin "2") (pinfunction "2_2") (pintype "passive"))
      (node (ref "U3") (pin "43") (pinfunction "SPI_SSEL_43") (pintype "passive"))
    )
    (net (code "65") (name "/SPI_MISO") (class "Default")
      (node (ref "U3") (pin "45") (pinfunction "SPI_SO_45") (pintype "passive+no_connect"))
    )
    (net (code "66") (name "/SPI_MOSI") (class "Default")
      (node (ref "U3") (pin "44") (pinfunction "SPI_SI_44") (pintype "passive+no_connect"))
    )
    (net (code "67") (name "/SPKL") (class "Default")
      (node (ref "P1") (pin "2") (pinfunction "2_2") (pintype "passive"))
      (node (ref "R20") (pin "2") (pinfunction "2_2") (pintype "passive"))
      (node (ref "U4") (pin "5") (pinfunction "2IN+_5") (pintype "passive"))
    )
    (net (code "68") (name "/SPKN") (class "Default")
      (node (ref "P1") (pin "1") (pinfunction "1_1") (pintype "passive"))
      (node (ref "U4") (pin "8") (pinfunction "VCC_8") (pintype "passive"))
    )
    (net (code "69") (name "/SS") (class "Default")
      (node (ref "C11") (pin "1") (pinfunction "1_1") (pintype "passive"))
      (node (ref "U7") (pin "2") (pinfunction "SO_2") (pintype "passive"))
    )
    (net (code "70") (name "/SWCLK") (class "Default")
      (node (ref "JP2") (pin "3") (pinfunction "3_3") (pintype "passive"))
      (node (ref "U1") (pin "109") (pinfunction "PA14/JTCK_SWCLK_109") (pintype "passive"))
    )
    (net (code "71") (name "/SWDIO") (class "Default")
      (node (ref "JP2") (pin "2") (pinfunction "2_2") (pintype "passive"))
      (node (ref "U1") (pin "105") (pinfunction "PA13/JTMS_SWDIO_105") (pintype "passive"))
    )
    (net (code "72") (name "/TXD") (class "Default")
      (node (ref "R118") (pin "2") (pinfunction "2_2") (pintype "passive"))
      (node (ref "U1") (pin "116") (pinfunction "PD2_116") (pintype "passive"))
      (node (ref "U3") (pin "41") (pinfunction "TXD_41") (pintype "passive"))
    )
    (net (code "73") (name "/USART1_RX") (class "Default")
      (node (ref "JP2") (pin "5") (pinfunction "5_5") (pintype "passive"))
      (node (ref "U1") (pin "102") (pinfunction "PA10/DCMI_D1_102") (pintype "passive"))
    )
    (net (code "74") (name "/USART1_TX") (class "Default")
      (node (ref "JP2") (pin "4") (pinfunction "4_4") (pintype "passive"))
      (node (ref "U1") (pin "101") (pinfunction "PA9/DCMI_D0_101") (pintype "passive"))
    )
    (net (code "75") (name "/USART3_RX") (class "Default")
      (node (ref "U1") (pin "70") (pinfunction "PB11/I2C2_SDA_70") (pintype "passive"))
      (node (ref "U6") (pin "19") (pinfunction "UART0_TX/GPIO01_19") (pintype "passive"))
    )
    (net (code "76") (name "/USART3_TX") (class "Default")
      (node (ref "U1") (pin "69") (pinfunction "PB10/I2C2_SCL_69") (pintype "passive"))
      (node (ref "U6") (pin "20") (pinfunction "UART0_RX/GPIO02_20") (pintype "passive"))
    )
    (net (code "77") (name "/USART4_RX") (class "Default")
      (node (ref "P3") (pin "5") (pinfunction "5_5") (pintype "passive"))
      (node (ref "U1") (pin "35") (pinfunction "PA1/ADC123_IN1_35") (pintype "passive"))
    )
    (net (code "78") (name "/USART4_TX") (class "Default")
      (node (ref "P3") (pin "4") (pinfunction "4_4") (pintype "passive"))
      (node (ref "U1") (pin "34") (pinfunction "PA0/ADC123_IN0_34") (pintype "passive"))
    )
    (net (code "79") (name "/VDDA") (class "Default")
      (node (ref "C23") (pin "2") (pintype "passive"))
      (node (ref "C24") (pin "2") (pintype "passive"))
      (node (ref "JP1") (pin "2") (pinfunction "2_2") (pintype "passive"))
      (node (ref "R18") (pin "2") (pinfunction "2_2") (pintype "passive"))
      (node (ref "U1") (pin "33") (pinfunction "VDDA_33") (pintype "passive"))
    )
    (net (code "80") (name "/VREF") (class "Default")
      (node (ref "C44") (pin "1") (pinfunction "1_1") (pintype "passive"))
      (node (ref "U3") (pin "18") (pinfunction "VREF_18") (pintype "passive"))
    )
    (net (code "81") (name "/VREF+") (class "Default")
      (node (ref "C7") (pin "2") (pinfunction "2_2") (pintype "passive"))
      (node (ref "JP1") (pin "1") (pinfunction "1_1") (pintype "passive"))
      (node (ref "U1") (pin "32") (pinfunction "VREF+_32") (pintype "passive"))
    )
    (net (code "82") (name "/nlink") (class "Default")
      (node (ref "D3") (pin "K") (pinfunction "K_K") (pintype "passive"))
      (node (ref "U6") (pin "23") (pinfunction "nLink/GPIO05_23") (pintype "passive"))
    )
    (net (code "83") (name "/nready") (class "Default")
      (node (ref "D1") (pin "K") (pinfunction "K_K") (pintype "passive"))
      (node (ref "U6") (pin "22") (pinfunction "nReady/GPIO04_22") (pintype "passive"))
    )
    (net (code "84") (name "3V3") (class "Default")
      (node (ref "C10") (pin "1") (pintype "passive"))
      (node (ref "C2") (pin "1") (pinfunction "VCC_1") (pintype "passive"))
      (node (ref "C28") (pin "2") (pinfunction "2_2") (pintype "passive"))
      (node (ref "C29") (pin "2") (pinfunction "2_2") (pintype "passive"))
      (node (ref "C30") (pin "2") (pinfunction "2_2") (pintype "passive"))
      (node (ref "C31") (pin "2") (pinfunction "2_2") (pintype "passive"))
      (node (ref "C32") (pin "2") (pinfunction "2_2") (pintype "passive"))
      (node (ref "C33") (pin "2") (pinfunction "2_2") (pintype "passive"))
      (node (ref "C34") (pin "2") (pinfunction "2_2") (pintype "passive"))
      (node (ref "C35") (pin "2") (pinfunction "2_2") (pintype "passive"))
      (node (ref "C4") (pin "2") (pintype "passive"))
      (node (ref "C45") (pin "1") (pinfunction "1_1") (pintype "passive"))
      (node (ref "C47") (pin "1") (pinfunction "1_1") (pintype "passive"))
      (node (ref "C48") (pin "1") (pinfunction "1_1") (pintype "passive"))
      (node (ref "C5") (pin "2") (pinfunction "2_2") (pintype "passive"))
      (node (ref "C8") (pin "2") (pintype "passive"))
      (node (ref "JP2") (pin "1") (pinfunction "1_1") (pintype "passive"))
      (node (ref "JP3") (pin "4") (pinfunction "4_4") (pintype "passive"))
      (node (ref "P3") (pin "2") (pinfunction "2_2") (pintype "passive"))
      (node (ref "R10") (pin "2") (pinfunction "2_2") (pintype "passive"))
      (node (ref "R17") (pin "1") (pinfunction "1_1") (pintype "passive"))
      (node (ref "R18") (pin "1") (pinfunction "1_1") (pintype "passive"))
      (node (ref "R2") (pin "2") (pinfunction "2_2") (pintype "passive"))
      (node (ref "R3") (pin "1") (pinfunction "1_1") (pintype "passive"))
      (node (ref "R5") (pin "2") (pinfunction "2_2") (pintype "passive"))
      (node (ref "R8") (pin "1") (pinfunction "1_1") (pintype "passive"))
      (node (ref "TFTLCD") (pin "24") (pinfunction "VDD3.3_24") (pintype "passive"))
      (node (ref "TFTLCD") (pin "25") (pinfunction "VDD3.3_25") (pintype "passive"))
      (node (ref "U1") (pin "108") (pinfunction "VDD2_108") (pintype "passive"))
      (node (ref "U1") (pin "121") (pinfunction "VDD10_121") (pintype "passive"))
      (node (ref "U1") (pin "131") (pinfunction "VDD11_131") (pintype "passive"))
      (node (ref "U1") (pin "144") (pinfunction "VDD3_144") (pintype "passive"))
      (node (ref "U1") (pin "17") (pinfunction "VDD5_17") (pintype "passive"))
      (node (ref "U1") (pin "30") (pinfunction "VDD12_30") (pintype "passive"))
      (node (ref "U1") (pin "39") (pinfunction "VDD4_39") (pintype "passive"))
      (node (ref "U1") (pin "52") (pinfunction "VDD6_52") (pintype "passive"))
      (node (ref "U1") (pin "62") (pinfunction "VDD7_62") (pintype "passive"))
      (node (ref "U1") (pin "72") (pinfunction "VDD1_72") (pintype "passive"))
      (node (ref "U1") (pin "84") (pinfunction "VDD8_84") (pintype "passive"))
      (node (ref "U1") (pin "95") (pinfunction "VDD9_95") (pintype "passive"))
      (node (ref "U2") (pin "2") (pinfunction "OUT_2") (pintype "passive"))
      (node (ref "U2") (pin "4") (pinfunction "OUT_4") (pintype "passive"))
      (node (ref "U3") (pin "20") (pinfunction "PWR_IN_20") (pintype "passive"))
      (node (ref "U4") (pin "6") (pinfunction "2IN-_6") (pintype "passive"))
      (node (ref "U6") (pin "13") (pinfunction "VBT_CC_13") (pintype "passive"))
      (node (ref "U6") (pin "14") (pinfunction "VDD_ANT_14") (pintype "passive"))
      (node (ref "W25Q128") (pin "3") (pinfunction "WP(IO2)_3") (pintype "passive"))
      (node (ref "W25Q128") (pin "7") (pinfunction "HOLD(IO3)_7") (pintype "passive"))
      (node (ref "W25Q128") (pin "8") (pinfunction "VCC_8") (pintype "passive"))
    )
    (net (code "85") (name "GND") (class "Default")
      (node (ref "C1") (pin "2") (pinfunction "GND_2") (pintype "passive"))
      (node (ref "C10") (pin "2") (pintype "passive"))
      (node (ref "C11") (pin "2") (pinfunction "2_2") (pintype "passive"))
      (node (ref "C12") (pin "1") (pintype "passive"))
      (node (ref "C127") (pin "1") (pinfunction "1_1") (pintype "passive"))
      (node (ref "C128") (pin "1") (pinfunction "1_1") (pintype "passive"))
      (node (ref "C129") (pin "1") (pinfunction "1_1") (pintype "passive"))
      (node (ref "C13") (pin "1") (pintype "passive"))
      (node (ref "C130") (pin "2") (pinfunction "2_2") (pintype "passive"))
      (node (ref "C131") (pin "1") (pinfunction "1_1") (pintype "passive"))
      (node (ref "C132") (pin "2") (pinfunction "2_2") (pintype "passive"))
      (node (ref "C133") (pin "1") (pinfunction "1_1") (pintype "passive"))
      (node (ref "C134") (pin "2") (pinfunction "2_2") (pintype "passive"))
      (node (ref "C135") (pin "1") (pinfunction "1_1") (pintype "passive"))
      (node (ref "C136") (pin "2") (pinfunction "2_2") (pintype "passive"))
      (node (ref "C137") (pin "1") (pinfunction "1_1") (pintype "passive"))
      (node (ref "C14") (pin "2") (pintype "passive"))
      (node (ref "C15") (pin "1") (pinfunction "1_1") (pintype "passive"))
      (node (ref "C2") (pin "2") (pinfunction "GND_2") (pintype "passive"))
      (node (ref "C22") (pin "2") (pintype "passive"))
      (node (ref "C23") (pin "1") (pintype "passive"))
      (node (ref "C24") (pin "1") (pintype "passive"))
      (node (ref "C25") (pin "2") (pintype "passive"))
      (node (ref "C27") (pin "2") (pintype "passive"))
      (node (ref "C28") (pin "1") (pinfunction "1_1") (pintype "passive"))
      (node (ref "C29") (pin "1") (pinfunction "1_1") (pintype "passive"))
      (node (ref "C3") (pin "1") (pintype "passive"))
      (node (ref "C30") (pin "1") (pinfunction "1_1") (pintype "passive"))
      (node (ref "C31") (pin "1") (pinfunction "1_1") (pintype "passive"))
      (node (ref "C32") (pin "1") (pinfunction "1_1") (pintype "passive"))
      (node (ref "C33") (pin "1") (pinfunction "1_1") (pintype "passive"))
      (node (ref "C34") (pin "1") (pinfunction "1_1") (pintype "passive"))
      (node (ref "C35") (pin "1") (pinfunction "1_1") (pintype "passive"))
      (node (ref "C39") (pin "2") (pinfunction "2_2") (pintype "passive"))
      (node (ref "C4") (pin "1") (pintype "passive"))
      (node (ref "C40") (pin "2") (pinfunction "2_2") (pintype "passive"))
      (node (ref "C43") (pin "1") (pinfunction "1_1") (pintype "passive"))
      (node (ref "C44") (pin "2") (pinfunction "2_2") (pintype "passive"))
      (node (ref "C45") (pin "2") (pinfunction "2_2") (pintype "passive"))
      (node (ref "C46") (pin "1") (pinfunction "1_1") (pintype "passive"))
      (node (ref "C48") (pin "2") (pinfunction "2_2") (pintype "passive"))
      (node (ref "C5") (pin "1") (pinfunction "1_1") (pintype "passive"))
      (node (ref "C6") (pin "1") (pinfunction "1_1") (pintype "passive"))
      (node (ref "C7") (pin "1") (pinfunction "1_1") (pintype "passive"))
      (node (ref "C8") (pin "1") (pintype "passive"))
      (node (ref "C9") (pin "2") (pintype "passive"))
      (node (ref "D5") (pin "K") (pinfunction "K_K") (pintype "passive"))
      (node (ref "JP2") (pin "6") (pinfunction "6_6") (pintype "passive"))
      (node (ref "JP3") (pin "1") (pinfunction "1_1") (pintype "passive"))
      (node (ref "P3") (pin "3") (pinfunction "3_3") (pintype "passive"))
      (node (ref "R112") (pin "1") (pintype "passive"))
      (node (ref "R115") (pin "1") (pinfunction "1_1") (pintype "passive"))
      (node (ref "R12") (pin "2") (pinfunction "2_2") (pintype "passive"))
      (node (ref "R13") (pin "2") (pinfunction "2_2") (pintype "passive"))
      (node (ref "R16") (pin "1") (pinfunction "1_1") (pintype "passive"))
      (node (ref "R25") (pin "1") (pinfunction "1_1") (pintype "passive"))
      (node (ref "R28") (pin "2") (pinfunction "2_2") (pintype "passive"))
      (node (ref "R4") (pin "2") (pinfunction "2_2") (pintype "passive"))
      (node (ref "R6") (pin "1") (pinfunction "1_1") (pintype "passive"))
      (node (ref "R7") (pin "1") (pinfunction "1_1") (pintype "passive"))
      (node (ref "R9") (pin "1") (pinfunction "1_1") (pintype "passive"))
      (node (ref "RESET") (pin "2") (pinfunction "2_2") (pintype "passive"))
      (node (ref "TFTLCD") (pin "22") (pinfunction "GND_22") (pintype "passive"))
      (node (ref "TFTLCD") (pin "26") (pinfunction "GND_26") (pintype "passive"))
      (node (ref "TFTLCD") (pin "27") (pinfunction "GND_27") (pintype "passive"))
      (node (ref "U1") (pin "107") (pinfunction "VSS2_107") (pintype "passive"))
      (node (ref "U1") (pin "120") (pinfunction "VSS10_120") (pintype "passive"))
      (node (ref "U1") (pin "130") (pinfunction "VSS11_130") (pintype "passive"))
      (node (ref "U1") (pin "16") (pinfunction "VSS5_16") (pintype "passive"))
      (node (ref "U1") (pin "31") (pinfunction "VSSA_31") (pintype "passive"))
      (node (ref "U1") (pin "38") (pinfunction "VSS4_38") (pintype "passive"))
      (node (ref "U1") (pin "51") (pinfunction "VSS6_51") (pintype "passive"))
      (node (ref "U1") (pin "61") (pinfunction "VSS7_61") (pintype "passive"))
      (node (ref "U1") (pin "83") (pinfunction "VSS8_83") (pintype "passive"))
      (node (ref "U1") (pin "94") (pinfunction "VSS9_94") (pintype "passive"))
      (node (ref "U2") (pin "1") (pinfunction "GND_1") (pintype "passive"))
      (node (ref "U3") (pin "10") (pinfunction "AGND_10") (pintype "passive"))
      (node (ref "U3") (pin "14") (pinfunction "AGND_14") (pintype "passive"))
      (node (ref "U3") (pin "25") (pinfunction "GND_25") (pintype "passive"))
      (node (ref "U3") (pin "37") (pinfunction "GND_37") (pintype "passive"))
      (node (ref "U3") (pin "4") (pinfunction "GND_4") (pintype "passive"))
      (node (ref "U3") (pin "52") (pinfunction "GND_52") (pintype "passive"))
      (node (ref "U3") (pin "64") (pinfunction "GND_64") (pintype "passive"))
      (node (ref "U5") (pin "1") (pinfunction "GND_1") (pintype "passive"))
      (node (ref "U6") (pin "1") (pinfunction "GND_1") (pintype "passive"))
      (node (ref "U6") (pin "11") (pinfunction "GND_11") (pintype "passive"))
      (node (ref "U6") (pin "12") (pinfunction "GND_12") (pintype "passive"))
      (node (ref "U6") (pin "17") (pinfunction "GND_17") (pintype "passive"))
      (node (ref "U6") (pin "28") (pinfunction "GND_28") (pintype "passive"))
      (node (ref "U6") (pin "29") (pinfunction "GND_29") (pintype "passive"))
      (node (ref "U6") (pin "44") (pinfunction "GND_44") (pintype "passive"))
      (node (ref "U6") (pin "45") (pinfunction "GND_45") (pintype "passive"))
      (node (ref "U7") (pin "1") (pinfunction "CS_1") (pintype "passive"))
      (node (ref "W25Q128") (pin "4") (pinfunction "GND_4") (pintype "passive"))
    )
    (net (code "86") (name "GND1") (class "Default")
      (node (ref "C41") (pin "2") (pinfunction "2_2") (pintype "passive"))
      (node (ref "C47") (pin "2") (pinfunction "2_2") (pintype "passive"))
      (node (ref "R9") (pin "2") (pinfunction "2_2") (pintype "passive"))
      (node (ref "U4") (pin "1") (pinfunction "1OUT_1") (pintype "passive"))
      (node (ref "U4") (pin "7") (pinfunction "2OUT_7") (pintype "passive"))
    )
    (net (code "87") (name "Net-(D1-PadA)") (class "Default")
      (node (ref "D1") (pin "A") (pinfunction "A_A") (pintype "passive"))
      (node (ref "R5") (pin "1") (pinfunction "1_1") (pintype "passive"))
    )
    (net (code "88") (name "Net-(D2-PadA)") (class "Default")
      (node (ref "D2") (pin "A") (pinfunction "A_A") (pintype "passive"))
      (node (ref "R17") (pin "2") (pinfunction "2_2") (pintype "passive"))
    )
    (net (code "89") (name "Net-(D3-PadA)") (class "Default")
      (node (ref "D3") (pin "A") (pinfunction "A_A") (pintype "passive"))
      (node (ref "R10") (pin "1") (pinfunction "1_1") (pintype "passive"))
    )
    (net (code "90") (name "Net-(D4-PadK)") (class "Default")
      (node (ref "D4") (pin "K") (pinfunction "K_K") (pintype "passive"))
      (node (ref "R6") (pin "2") (pinfunction "2_2") (pintype "passive"))
    )
    (net (code "91") (name "Net-(D5-PadA)") (class "Default")
      (node (ref "D5") (pin "A") (pinfunction "A_A") (pintype "passive"))
      (node (ref "R8") (pin "2") (pinfunction "2_2") (pintype "passive"))
    )
    (net (code "92") (name "Net-(K1-COMMON)") (class "Default")
      (node (ref "K1") (pin "1") (pinfunction "COMMON_1") (pintype "passive"))
      (node (ref "U5") (pin "4") (pinfunction "VCC_4") (pintype "passive"))
    )
    (net (code "93") (name "Net-(P2-Pad1)") (class "Default")
      (node (ref "P2") (pin "1") (pinfunction "1_1") (pintype "passive"))
      (node (ref "R7") (pin "2") (pinfunction "2_2") (pintype "passive"))
    )
    (net (code "94") (name "Net-(P2-Pad2)") (class "Default")
      (node (ref "P2") (pin "2") (pinfunction "2_2") (pintype "passive"))
      (node (ref "R4") (pin "1") (pinfunction "1_1") (pintype "passive"))
    )
    (net (code "95") (name "Net-(P2-Pad5)") (class "Default")
      (node (ref "P2") (pin "5") (pinfunction "5_5") (pintype "passive"))
      (node (ref "R3") (pin "2") (pinfunction "2_2") (pintype "passive"))
    )
    (net (code "96") (name "Net-(P2-Pad6)") (class "Default")
      (node (ref "P2") (pin "6") (pinfunction "6_6") (pintype "passive"))
      (node (ref "R2") (pin "1") (pinfunction "1_1") (pintype "passive"))
    )
    (net (code "97") (name "Net-(U1B-PDR_ON)") (class "Default")
      (node (ref "R16") (pin "2") (pinfunction "2_2") (pintype "passive"))
      (node (ref "U1") (pin "143") (pinfunction "PDR_ON_143") (pintype "passive"))
    )
    (net (code "98") (name "Net-(U1B-VCAP_1)") (class "Default")
      (node (ref "C25") (pin "1") (pintype "passive"))
      (node (ref "U1") (pin "71") (pinfunction "VCAP_1_71") (pintype "passive"))
    )
    (net (code "99") (name "Net-(U1B-VCAP_2)") (class "Default")
      (node (ref "C27") (pin "1") (pintype "passive"))
      (node (ref "U1") (pin "106") (pinfunction "VCAP_2_106") (pintype "passive"))
    )
    (net (code "100") (name "Net-(U3-A1)") (class "Default")
      (node (ref "U3") (pin "53") (pinfunction "A1_53") (pintype "passive"))
      (node (ref "U3") (pin "54") (pinfunction "A2_54") (pintype "passive"))
    )
    (net (code "101") (name "Net-(U3-AO_P)") (class "Default")
      (node (ref "C38") (pin "2") (pinfunction "2_2") (pintype "passive"))
      (node (ref "U3") (pin "8") (pinfunction "AO_P_8") (pintype "passive"))
    )
    (net (code "102") (name "Net-(U3-RREF)") (class "Default")
      (node (ref "R115") (pin "2") (pinfunction "2_2") (pintype "passive"))
      (node (ref "U3") (pin "3") (pinfunction "RREF_3") (pintype "passive"))
    )
    (net (code "103") (name "Net-(U3-VCM)") (class "Default")
      (node (ref "C40") (pin "1") (pinfunction "1_1") (pintype "passive"))
      (node (ref "U3") (pin "11") (pinfunction "VCM_11") (pintype "passive"))
    )
    (net (code "104") (name "Net-(U4-1IN+)") (class "Default")
      (node (ref "C41") (pin "1") (pinfunction "1_1") (pintype "passive"))
      (node (ref "U4") (pin "2") (pinfunction "1IN-_2") (pintype "passive"))
      (node (ref "U4") (pin "3") (pinfunction "1IN+_3") (pintype "passive"))
    )
    (net (code "105") (name "Net-(U4-GND)") (class "Default")
      (node (ref "R1") (pin "2") (pinfunction "2_2") (pintype "passive"))
      (node (ref "R20") (pin "1") (pinfunction "1_1") (pintype "passive"))
      (node (ref "U4") (pin "4") (pinfunction "GND_4") (pintype "passive"))
    )
    (net (code "106") (name "Net-(U6-ANT_DC)") (class "Default")
      (node (ref "C6") (pin "2") (pinfunction "2_2") (pintype "passive"))
      (node (ref "U6") (pin "8") (pinfunction "ANT_DC_8") (pintype "passive"))
    )
    (net (code "107") (name "VDD12") (class "Default")
      (node (ref "C128") (pin "2") (pinfunction "2_2") (pintype "passive"))
      (node (ref "C134") (pin "1") (pinfunction "1_1") (pintype "passive"))
      (node (ref "C135") (pin "2") (pinfunction "2_2") (pintype "passive"))
      (node (ref "U3") (pin "1") (pinfunction "VDD12_1") (pintype "passive"))
      (node (ref "U3") (pin "23") (pinfunction "VDD12_O_23") (pintype "passive"))
    )
    (net (code "108") (name "VDD33") (class "Default")
      (node (ref "C127") (pin "2") (pinfunction "2_2") (pintype "passive"))
      (node (ref "C129") (pin "2") (pinfunction "2_2") (pintype "passive"))
      (node (ref "C130") (pin "1") (pinfunction "1_1") (pintype "passive"))
      (node (ref "C131") (pin "2") (pinfunction "2_2") (pintype "passive"))
      (node (ref "FB1") (pin "2") (pinfunction "2_2") (pintype "passive"))
      (node (ref "R116") (pin "2") (pintype "passive"))
      (node (ref "R118") (pin "1") (pinfunction "1_1") (pintype "passive"))
      (node (ref "R19") (pin "2") (pinfunction "2_2") (pintype "passive"))
      (node (ref "R21") (pin "1") (pinfunction "1_1") (pintype "passive"))
      (node (ref "R23") (pin "1") (pinfunction "1_1") (pintype "passive"))
      (node (ref "R24") (pin "1") (pinfunction "1_1") (pintype "passive"))
      (node (ref "R26") (pin "1") (pinfunction "1_1") (pintype "passive"))
      (node (ref "R27") (pin "1") (pinfunction "1_1") (pintype "passive"))
      (node (ref "U3") (pin "22") (pinfunction "VDD33_O_22") (pintype "passive"))
      (node (ref "U3") (pin "36") (pinfunction "VDD33_36") (pintype "passive"))
      (node (ref "U3") (pin "46") (pinfunction "VDD33_46") (pintype "passive"))
    )
    (net (code "109") (name "unconnected-(P3-Pad1)") (class "Default")
      (node (ref "P3") (pin "1") (pinfunction "1_1") (pintype "passive"))
    )
    (net (code "110") (name "unconnected-(P3-Pad6)") (class "Default")
      (node (ref "P3") (pin "6") (pinfunction "6_6") (pintype "passive"))
    )
    (net (code "111") (name "unconnected-(P3-Pad7)") (class "Default")
      (node (ref "P3") (pin "7") (pinfunction "7_7") (pintype "passive"))
    )
    (net (code "112") (name "unconnected-(P3-Pad8)") (class "Default")
      (node (ref "P3") (pin "8") (pinfunction "8_8") (pintype "passive"))
    )
    (net (code "113") (name "unconnected-(P3-Pad9)") (class "Default")
      (node (ref "P3") (pin "9") (pinfunction "9_9") (pintype "passive"))
    )
    (net (code "114") (name "unconnected-(P3-Pad10)") (class "Default")
      (node (ref "P3") (pin "10") (pinfunction "10_10") (pintype "passive"))
    )
    (net (code "115") (name "unconnected-(P3-Pad11)") (class "Default")
      (node (ref "P3") (pin "11") (pinfunction "11_11") (pintype "passive"))
    )
    (net (code "116") (name "unconnected-(P3-Pad12)") (class "Default")
      (node (ref "P3") (pin "12") (pinfunction "12_12") (pintype "passive"))
    )
    (net (code "117") (name "unconnected-(TFTLCD-MO-Pad32)") (class "Default")
      (node (ref "TFTLCD") (pin "32") (pinfunction "MO_32") (pintype "passive+no_connect"))
    )
    (net (code "118") (name "unconnected-(U1A-PA2{slash}USART2_TX{slash}ADC123_IN2-Pad36)") (class "Default")
      (node (ref "U1") (pin "36") (pinfunction "PA2/USART2_TX/ADC123_IN2_36") (pintype "passive"))
    )
    (net (code "119") (name "unconnected-(U1A-PA3{slash}USART2_RX{slash}ADC123_IN3-Pad37)") (class "Default")
      (node (ref "U1") (pin "37") (pinfunction "PA3/USART2_RX/ADC123_IN3_37") (pintype "passive"))
    )
    (net (code "120") (name "unconnected-(U1A-PA4{slash}DCMI_HSYNC{slash}DAC1{slash}ADC12_IN4-Pad40)") (class "Default")
      (node (ref "U1") (pin "40") (pinfunction "PA4/DCMI_HSYNC/DAC1/ADC12_IN4_40") (pintype "passive"))
    )
    (net (code "121") (name "unconnected-(U1A-PA5{slash}SPI1_SCK{slash}DAC2{slash}ADC12_IN5-Pad41)") (class "Default")
      (node (ref "U1") (pin "41") (pinfunction "PA5/SPI1_SCK/DAC2/ADC12_IN5_41") (pintype "passive"))
    )
    (net (code "122") (name "unconnected-(U1A-PA6{slash}DCMI_PIXCK{slash}ADC12_IN6-Pad42)") (class "Default")
      (node (ref "U1") (pin "42") (pinfunction "PA6/DCMI_PIXCK/ADC12_IN6_42") (pintype "passive"))
    )
    (net (code "123") (name "unconnected-(U1A-PA7{slash}SPI1_MOSI{slash}ADC12_IN7-Pad43)") (class "Default")
      (node (ref "U1") (pin "43") (pinfunction "PA7/SPI1_MOSI/ADC12_IN7_43") (pintype "passive"))
    )
    (net (code "124") (name "unconnected-(U1A-PA11{slash}USBDM-Pad103)") (class "Default")
      (node (ref "U1") (pin "103") (pinfunction "PA11/USBDM_103") (pintype "passive"))
    )
    (net (code "125") (name "unconnected-(U1A-PA12{slash}USBDP-Pad104)") (class "Default")
      (node (ref "U1") (pin "104") (pinfunction "PA12/USBDP_104") (pintype "passive"))
    )
    (net (code "126") (name "unconnected-(U1A-PA15{slash}SPI3_NSS-Pad110)") (class "Default")
      (node (ref "U1") (pin "110") (pinfunction "PA15/SPI3_NSS_110") (pintype "passive"))
    )
    (net (code "127") (name "unconnected-(U1A-PB6{slash}DCMI_D5{slash}USART1_TX-Pad136)") (class "Default")
      (node (ref "U1") (pin "136") (pinfunction "PB6/DCMI_D5/USART1_TX_136") (pintype "passive"))
    )
    (net (code "128") (name "unconnected-(U1A-PB7{slash}FSMC_NL{slash}DCMI_VSYNC{slash}USART1_RX-Pad137)") (class "Default")
      (node (ref "U1") (pin "137") (pinfunction "PB7/FSMC_NL/DCMI_VSYNC/USART1_RX_137") (pintype "passive"))
    )
    (net (code "129") (name "unconnected-(U1A-PB8{slash}DCMI_D6{slash}I2C1_SCL-Pad139)") (class "Default")
      (node (ref "U1") (pin "139") (pinfunction "PB8/DCMI_D6/I2C1_SCL_139") (pintype "passive"))
    )
    (net (code "130") (name "unconnected-(U1A-PB9{slash}DCMI_D7{slash}I2C1_SDA-Pad140)") (class "Default")
      (node (ref "U1") (pin "140") (pinfunction "PB9/DCMI_D7/I2C1_SDA_140") (pintype "passive"))
    )
    (net (code "131") (name "unconnected-(U1A-PB12{slash}SPI2_NSS{slash}I2C2_SMBAI-Pad73)") (class "Default")
      (node (ref "U1") (pin "73") (pinfunction "PB12/SPI2_NSS/I2C2_SMBAI_73") (pintype "passive"))
    )
    (net (code "132") (name "unconnected-(U1A-PB13{slash}SPI2_SCK-Pad74)") (class "Default")
      (node (ref "U1") (pin "74") (pinfunction "PB13/SPI2_SCK_74") (pintype "passive"))
    )
    (net (code "133") (name "unconnected-(U1A-PB15{slash}SPI2_MOSI{slash}I2S2_SD-Pad76)") (class "Default")
      (node (ref "U1") (pin "76") (pinfunction "PB15/SPI2_MOSI/I2S2_SD_76") (pintype "passive"))
    )
    (net (code "134") (name "unconnected-(U1A-PC0{slash}ADC123_IN10-Pad26)") (class "Default")
      (node (ref "U1") (pin "26") (pinfunction "PC0/ADC123_IN10_26") (pintype "passive"))
    )
    (net (code "135") (name "unconnected-(U1A-PC1{slash}ADC123_IN11-Pad27)") (class "Default")
      (node (ref "U1") (pin "27") (pinfunction "PC1/ADC123_IN11_27") (pintype "passive"))
    )
    (net (code "136") (name "unconnected-(U1A-PC2{slash}ADC123_IN12-Pad28)") (class "Default")
      (node (ref "U1") (pin "28") (pinfunction "PC2/ADC123_IN12_28") (pintype "passive"))
    )
    (net (code "137") (name "unconnected-(U1A-PC3{slash}ADC123_IN13-Pad29)") (class "Default")
      (node (ref "U1") (pin "29") (pinfunction "PC3/ADC123_IN13_29") (pintype "passive"))
    )
    (net (code "138") (name "unconnected-(U1A-PC4{slash}ADC123_IN14-Pad44)") (class "Default")
      (node (ref "U1") (pin "44") (pinfunction "PC4/ADC123_IN14_44") (pintype "passive"))
    )
    (net (code "139") (name "unconnected-(U1A-PC5{slash}ADC123_IN15-Pad45)") (class "Default")
      (node (ref "U1") (pin "45") (pinfunction "PC5/ADC123_IN15_45") (pintype "passive"))
    )
    (net (code "140") (name "unconnected-(U1A-PC6{slash}DCMI_D0-Pad96)") (class "Default")
      (node (ref "U1") (pin "96") (pinfunction "PC6/DCMI_D0_96") (pintype "passive"))
    )
    (net (code "141") (name "unconnected-(U1A-PC7{slash}DCMI_D1-Pad97)") (class "Default")
      (node (ref "U1") (pin "97") (pinfunction "PC7/DCMI_D1_97") (pintype "passive"))
    )
    (net (code "142") (name "unconnected-(U1A-PC8{slash}DCMI_D2-Pad98)") (class "Default")
      (node (ref "U1") (pin "98") (pinfunction "PC8/DCMI_D2_98") (pintype "passive"))
    )
    (net (code "143") (name "unconnected-(U1A-PC9{slash}DCMI_D3-Pad99)") (class "Default")
      (node (ref "U1") (pin "99") (pinfunction "PC9/DCMI_D3_99") (pintype "passive"))
    )
    (net (code "144") (name "unconnected-(U1A-PC10{slash}SPI3_SCK-Pad111)") (class "Default")
      (node (ref "U1") (pin "111") (pinfunction "PC10/SPI3_SCK_111") (pintype "passive"))
    )
    (net (code "145") (name "unconnected-(U1A-PC11{slash}DCMI_D4{slash}SPI3_MISO-Pad112)") (class "Default")
      (node (ref "U1") (pin "112") (pinfunction "PC11/DCMI_D4/SPI3_MISO_112") (pintype "passive"))
    )
    (net (code "146") (name "unconnected-(U1A-PC13-Pad7)") (class "Default")
      (node (ref "U1") (pin "7") (pinfunction "PC13_7") (pintype "passive"))
    )
    (net (code "147") (name "unconnected-(U1A-PD6{slash}FSMC_NWAIT-Pad122)") (class "Default")
      (node (ref "U1") (pin "122") (pinfunction "PD6/FSMC_NWAIT_122") (pintype "passive"))
    )
    (net (code "148") (name "unconnected-(U1A-PD7{slash}FSMC_NE1-Pad123)") (class "Default")
      (node (ref "U1") (pin "123") (pinfunction "PD7/FSMC_NE1_123") (pintype "passive"))
    )
    (net (code "149") (name "unconnected-(U1A-PD11{slash}FSMC_A16-Pad80)") (class "Default")
      (node (ref "U1") (pin "80") (pinfunction "PD11/FSMC_A16_80") (pintype "passive"))
    )
    (net (code "150") (name "unconnected-(U1A-PD12{slash}FSMC_A17-Pad81)") (class "Default")
      (node (ref "U1") (pin "81") (pinfunction "PD12/FSMC_A17_81") (pintype "passive"))
    )
    (net (code "151") (name "unconnected-(U1A-PD13{slash}FSMC_A18-Pad82)") (class "Default")
      (node (ref "U1") (pin "82") (pinfunction "PD13/FSMC_A18_82") (pintype "passive"))
    )
    (net (code "152") (name "unconnected-(U1A-PE0{slash}FSMC_NBL0{slash}DCMI_D2-Pad141)") (class "Default")
      (node (ref "U1") (pin "141") (pinfunction "PE0/FSMC_NBL0/DCMI_D2_141") (pintype "passive+no_connect"))
    )
    (net (code "153") (name "unconnected-(U1A-PE1{slash}FSMC_NBL1{slash}DCMI_D3-Pad142)") (class "Default")
      (node (ref "U1") (pin "142") (pinfunction "PE1/FSMC_NBL1/DCMI_D3_142") (pintype "passive+no_connect"))
    )
    (net (code "154") (name "unconnected-(U1A-PE2{slash}FSMC_A23-Pad1)") (class "Default")
      (node (ref "U1") (pin "1") (pinfunction "PE2/FSMC_A23_1") (pintype "passive"))
    )
    (net (code "155") (name "unconnected-(U1A-PE3{slash}FSMC_A19-Pad2)") (class "Default")
      (node (ref "U1") (pin "2") (pinfunction "PE3/FSMC_A19_2") (pintype "passive"))
    )
    (net (code "156") (name "unconnected-(U1A-PE4{slash}FSMC_A20{slash}DCMI_D4-Pad3)") (class "Default")
      (node (ref "U1") (pin "3") (pinfunction "PE4/FSMC_A20/DCMI_D4_3") (pintype "passive+no_connect"))
    )
    (net (code "157") (name "unconnected-(U1A-PE5{slash}FSMC_A21{slash}DCMI_D6-Pad4)") (class "Default")
      (node (ref "U1") (pin "4") (pinfunction "PE5/FSMC_A21/DCMI_D6_4") (pintype "passive+no_connect"))
    )
    (net (code "158") (name "unconnected-(U1A-PE6{slash}FSMC_A22{slash}DCMI_D7-Pad5)") (class "Default")
      (node (ref "U1") (pin "5") (pinfunction "PE6/FSMC_A22/DCMI_D7_5") (pintype "passive+no_connect"))
    )
    (net (code "159") (name "unconnected-(U1A-PF1{slash}FSMC_A1-Pad11)") (class "Default")
      (node (ref "U1") (pin "11") (pinfunction "PF1/FSMC_A1_11") (pintype "passive"))
    )
    (net (code "160") (name "unconnected-(U1A-PF2{slash}FSMC_A2-Pad12)") (class "Default")
      (node (ref "U1") (pin "12") (pinfunction "PF2/FSMC_A2_12") (pintype "passive"))
    )
    (net (code "161") (name "unconnected-(U1A-PF3{slash}FSMC_A23{slash}ADC3_IN9-Pad13)") (class "Default")
      (node (ref "U1") (pin "13") (pinfunction "PF3/FSMC_A23/ADC3_IN9_13") (pintype "passive"))
    )
    (net (code "162") (name "unconnected-(U1A-PF4{slash}FSMC_A4{slash}ADC3_IN14-Pad14)") (class "Default")
      (node (ref "U1") (pin "14") (pinfunction "PF4/FSMC_A4/ADC3_IN14_14") (pintype "passive"))
    )
    (net (code "163") (name "unconnected-(U1A-PF5{slash}FSMC_A5{slash}ADC3_IN15-Pad15)") (class "Default")
      (node (ref "U1") (pin "15") (pinfunction "PF5/FSMC_A5/ADC3_IN15_15") (pintype "passive"))
    )
    (net (code "164") (name "unconnected-(U1A-PF6{slash}FSMC_NIORD{slash}ADC3_IN4-Pad18)") (class "Default")
      (node (ref "U1") (pin "18") (pinfunction "PF6/FSMC_NIORD/ADC3_IN4_18") (pintype "passive"))
    )
    (net (code "165") (name "unconnected-(U1A-PF7{slash}FSMC_NREG{slash}ADC3_IN5-Pad19)") (class "Default")
      (node (ref "U1") (pin "19") (pinfunction "PF7/FSMC_NREG/ADC3_IN5_19") (pintype "passive"))
    )
    (net (code "166") (name "unconnected-(U1A-PF11-Pad49)") (class "Default")
      (node (ref "U1") (pin "49") (pinfunction "PF11_49") (pintype "passive"))
    )
    (net (code "167") (name "unconnected-(U1A-PF13{slash}FSMC_A7-Pad53)") (class "Default")
      (node (ref "U1") (pin "53") (pinfunction "PF13/FSMC_A7_53") (pintype "passive"))
    )
    (net (code "168") (name "unconnected-(U1A-PF14{slash}FSMC_A8-Pad54)") (class "Default")
      (node (ref "U1") (pin "54") (pinfunction "PF14/FSMC_A8_54") (pintype "passive"))
    )
    (net (code "169") (name "unconnected-(U1A-PF15{slash}FSMC_A9-Pad55)") (class "Default")
      (node (ref "U1") (pin "55") (pinfunction "PF15/FSMC_A9_55") (pintype "passive"))
    )
    (net (code "170") (name "unconnected-(U1A-PG0{slash}FSMC_A10-Pad56)") (class "Default")
      (node (ref "U1") (pin "56") (pinfunction "PG0/FSMC_A10_56") (pintype "passive"))
    )
    (net (code "171") (name "unconnected-(U1A-PG1{slash}FSMC_A11-Pad57)") (class "Default")
      (node (ref "U1") (pin "57") (pinfunction "PG1/FSMC_A11_57") (pintype "passive"))
    )
    (net (code "172") (name "unconnected-(U1A-PG2{slash}FSMC_A12-Pad87)") (class "Default")
      (node (ref "U1") (pin "87") (pinfunction "PG2/FSMC_A12_87") (pintype "passive"))
    )
    (net (code "173") (name "unconnected-(U1A-PG3{slash}FSMC_A13-Pad88)") (class "Default")
      (node (ref "U1") (pin "88") (pinfunction "PG3/FSMC_A13_88") (pintype "passive"))
    )
    (net (code "174") (name "unconnected-(U1A-PG4{slash}FSMC_A14-Pad89)") (class "Default")
      (node (ref "U1") (pin "89") (pinfunction "PG4/FSMC_A14_89") (pintype "passive"))
    )
    (net (code "175") (name "unconnected-(U1A-PG5{slash}FSMC_A15-Pad90)") (class "Default")
      (node (ref "U1") (pin "90") (pinfunction "PG5/FSMC_A15_90") (pintype "passive"))
    )
    (net (code "176") (name "unconnected-(U1A-PG6{slash}FSMC_INT2-Pad91)") (class "Default")
      (node (ref "U1") (pin "91") (pinfunction "PG6/FSMC_INT2_91") (pintype "passive"))
    )
    (net (code "177") (name "unconnected-(U1A-PG7{slash}FSMC_INT3-Pad92)") (class "Default")
      (node (ref "U1") (pin "92") (pinfunction "PG7/FSMC_INT3_92") (pintype "passive"))
    )
    (net (code "178") (name "unconnected-(U1A-PG8-Pad93)") (class "Default")
      (node (ref "U1") (pin "93") (pinfunction "PG8_93") (pintype "passive"))
    )
    (net (code "179") (name "unconnected-(U1A-PG9{slash}FSMC_NE2-Pad124)") (class "Default")
      (node (ref "U1") (pin "124") (pinfunction "PG9/FSMC_NE2_124") (pintype "passive"))
    )
    (net (code "180") (name "unconnected-(U1A-PG10{slash}FSMC_NE3-Pad125)") (class "Default")
      (node (ref "U1") (pin "125") (pinfunction "PG10/FSMC_NE3_125") (pintype "passive+no_connect"))
    )
    (net (code "181") (name "unconnected-(U1A-PG11{slash}FSMC_NCE4_2-Pad126)") (class "Default")
      (node (ref "U1") (pin "126") (pinfunction "PG11/FSMC_NCE4_2_126") (pintype "passive"))
    )
    (net (code "182") (name "unconnected-(U1A-PG13{slash}FSMC_A24-Pad128)") (class "Default")
      (node (ref "U1") (pin "128") (pinfunction "PG13/FSMC_A24_128") (pintype "passive"))
    )
    (net (code "183") (name "unconnected-(U1A-PG14{slash}FSMC_A25-Pad129)") (class "Default")
      (node (ref "U1") (pin "129") (pinfunction "PG14/FSMC_A25_129") (pintype "passive"))
    )
    (net (code "184") (name "unconnected-(U1A-PG15-Pad132)") (class "Default")
      (node (ref "U1") (pin "132") (pinfunction "PG15_132") (pintype "passive+no_connect"))
    )
    (net (code "185") (name "unconnected-(U1B-VBAT-Pad6)") (class "Default")
      (node (ref "U1") (pin "6") (pinfunction "VBAT_6") (pintype "passive+no_connect"))
    )
    (net (code "186") (name "unconnected-(U3-AO_N-Pad9)") (class "Default")
      (node (ref "U3") (pin "9") (pinfunction "AO_N_9") (pintype "passive"))
    )
    (net (code "187") (name "unconnected-(U3-MIC_N-Pad13)") (class "Default")
      (node (ref "U3") (pin "13") (pinfunction "MIC_N_13") (pintype "passive"))
    )
    (net (code "188") (name "unconnected-(U3-MIC_P-Pad15)") (class "Default")
      (node (ref "U3") (pin "15") (pinfunction "MIC_P_15") (pintype "passive"))
    )
    (net (code "189") (name "unconnected-(U3-NC-Pad5)") (class "Default")
      (node (ref "U3") (pin "5") (pinfunction "NC_5") (pintype "passive+no_connect"))
    )
    (net (code "190") (name "unconnected-(U3-NC-Pad6)") (class "Default")
      (node (ref "U3") (pin "6") (pinfunction "NC_6") (pintype "passive+no_connect"))
    )
    (net (code "191") (name "unconnected-(U3-NC-Pad19)") (class "Default")
      (node (ref "U3") (pin "19") (pinfunction "NC_19") (pintype "passive+no_connect"))
    )
    (net (code "192") (name "unconnected-(U3-NC-Pad30)") (class "Default")
      (node (ref "U3") (pin "30") (pinfunction "NC_30") (pintype "passive+no_connect"))
    )
    (net (code "193") (name "unconnected-(U3-NC-Pad31)") (class "Default")
      (node (ref "U3") (pin "31") (pinfunction "NC_31") (pintype "passive+no_connect"))
    )
    (net (code "194") (name "unconnected-(U3-NC-Pad32)") (class "Default")
      (node (ref "U3") (pin "32") (pinfunction "NC_32") (pintype "passive+no_connect"))
    )
    (net (code "195") (name "unconnected-(U3-NC-Pad33)") (class "Default")
      (node (ref "U3") (pin "33") (pinfunction "NC_33") (pintype "passive+no_connect"))
    )
    (net (code "196") (name "unconnected-(U3-NC-Pad34)") (class "Default")
      (node (ref "U3") (pin "34") (pinfunction "NC_34") (pintype "passive+no_connect"))
    )
    (net (code "197") (name "unconnected-(U3-NC-Pad35)") (class "Default")
      (node (ref "U3") (pin "35") (pinfunction "NC_35") (pintype "passive+no_connect"))
    )
    (net (code "198") (name "unconnected-(U3-NC-Pad38)") (class "Default")
      (node (ref "U3") (pin "38") (pinfunction "NC_38") (pintype "passive+no_connect"))
    )
    (net (code "199") (name "unconnected-(U3-NC-Pad58)") (class "Default")
      (node (ref "U3") (pin "58") (pinfunction "NC_58") (pintype "passive+no_connect"))
    )
    (net (code "200") (name "unconnected-(U3-NC-Pad61)") (class "Default")
      (node (ref "U3") (pin "61") (pinfunction "NC_61") (pintype "passive+no_connect"))
    )
    (net (code "201") (name "unconnected-(U3-NC-Pad63)") (class "Default")
      (node (ref "U3") (pin "63") (pinfunction "NC_63") (pintype "passive+no_connect"))
    )
    (net (code "202") (name "unconnected-(U5-D+-Pad2)") (class "Default")
      (node (ref "U5") (pin "2") (pinfunction "D+_2") (pintype "passive"))
    )
    (net (code "203") (name "unconnected-(U5-D--Pad3)") (class "Default")
      (node (ref "U5") (pin "3") (pinfunction "D-_3") (pintype "passive"))
    )
    (net (code "204") (name "unconnected-(U6-GPIO00-Pad18)") (class "Default")
      (node (ref "U6") (pin "18") (pinfunction "GPIO00_18") (pintype "passive"))
    )
    (net (code "205") (name "unconnected-(U6-GPIO08-Pad26)") (class "Default")
      (node (ref "U6") (pin "26") (pinfunction "GPIO08_26") (pintype "passive"))
    )
    (net (code "206") (name "unconnected-(U6-GPIO09-Pad27)") (class "Default")
      (node (ref "U6") (pin "27") (pinfunction "GPIO09_27") (pintype "passive"))
    )
    (net (code "207") (name "unconnected-(U6-GPIO12-Pad32)") (class "Default")
      (node (ref "U6") (pin "32") (pinfunction "GPIO12_32") (pintype "passive"))
    )
    (net (code "208") (name "unconnected-(U6-GPIO22-Pad38)") (class "Default")
      (node (ref "U6") (pin "38") (pinfunction "GPIO22_38") (pintype "passive"))
    )
    (net (code "209") (name "unconnected-(U6-GPIO28-Pad41)") (class "Default")
      (node (ref "U6") (pin "41") (pinfunction "GPIO28_41") (pintype "passive"))
    )
    (net (code "210") (name "unconnected-(U6-GPIO30-Pad15)") (class "Default")
      (node (ref "U6") (pin "15") (pinfunction "GPIO30_15") (pintype "passive"))
    )
    (net (code "211") (name "unconnected-(U6-JTAG_TCK-Pad42)") (class "Default")
      (node (ref "U6") (pin "42") (pinfunction "JTAG_TCK_42") (pintype "passive"))
    )
    (net (code "212") (name "unconnected-(U6-JTAG_TDI-Pad39)") (class "Default")
      (node (ref "U6") (pin "39") (pinfunction "JTAG_TDI_39") (pintype "passive"))
    )
    (net (code "213") (name "unconnected-(U6-JTAG_TDO-Pad40)") (class "Default")
      (node (ref "U6") (pin "40") (pinfunction "JTAG_TDO_40") (pintype "passive"))
    )
    (net (code "214") (name "unconnected-(U6-JTAG_TMS-Pad43)") (class "Default")
      (node (ref "U6") (pin "43") (pinfunction "JTAG_TMS_43") (pintype "passive"))
    )
    (net (code "215") (name "unconnected-(U6-NC-Pad9)") (class "Default")
      (node (ref "U6") (pin "9") (pinfunction "NC_9") (pintype "passive"))
    )
    (net (code "216") (name "unconnected-(U6-NC-Pad10)") (class "Default")
      (node (ref "U6") (pin "10") (pinfunction "NC_10") (pintype "passive"))
    )
    (net (code "217") (name "unconnected-(U6-NC-Pad16)") (class "Default")
      (node (ref "U6") (pin "16") (pinfunction "NC_16") (pintype "passive"))
    )
    (net (code "218") (name "unconnected-(U6-NC_ATNSEL1-Pad2)") (class "Default")
      (node (ref "U6") (pin "2") (pinfunction "NC_ATNSEL1_2") (pintype "passive"))
    )
    (net (code "219") (name "unconnected-(U6-NC_ATNSEL2-Pad3)") (class "Default")
      (node (ref "U6") (pin "3") (pinfunction "NC_ATNSEL2_3") (pintype "passive"))
    )
    (net (code "220") (name "unconnected-(U6-SOP0-Pad7)") (class "Default")
      (node (ref "U6") (pin "7") (pinfunction "SOP0_7") (pintype "passive"))
    )
    (net (code "221") (name "unconnected-(U6-SOP1-Pad6)") (class "Default")
      (node (ref "U6") (pin "6") (pinfunction "SOP1_6") (pintype "passive"))
    )
    (net (code "222") (name "unconnected-(U6-SOP2-Pad5)") (class "Default")
      (node (ref "U6") (pin "5") (pinfunction "SOP2_5") (pintype "passive"))
    )
    (net (code "223") (name "unconnected-(U6-SPI_CLK{slash}GPIO14-Pad34)") (class "Default")
      (node (ref "U6") (pin "34") (pinfunction "SPI_CLK/GPIO14_34") (pintype "passive"))
    )
    (net (code "224") (name "unconnected-(U6-SPI_CS{slash}GPIO17-Pad37)") (class "Default")
      (node (ref "U6") (pin "37") (pinfunction "SPI_CS/GPIO17_37") (pintype "passive"))
    )
    (net (code "225") (name "unconnected-(U6-SPI_IRQ{slash}GPIO13-Pad33)") (class "Default")
      (node (ref "U6") (pin "33") (pinfunction "SPI_IRQ/GPIO13_33") (pintype "passive"))
    )
    (net (code "226") (name "unconnected-(U6-SPI_MISO{slash}GPIO15-Pad35)") (class "Default")
      (node (ref "U6") (pin "35") (pinfunction "SPI_MISO/GPIO15_35") (pintype "passive"))
    )
    (net (code "227") (name "unconnected-(U6-SPI_MOSI{slash}GPIO16-Pad36)") (class "Default")
      (node (ref "U6") (pin "36") (pinfunction "SPI_MOSI/GPIO16_36") (pintype "passive"))
    )
    (net (code "228") (name "unconnected-(U6-UART0_CTS{slash}GPIO06-Pad24)") (class "Default")
      (node (ref "U6") (pin "24") (pinfunction "UART0_CTS/GPIO06_24") (pintype "passive"))
    )
    (net (code "229") (name "unconnected-(U6-UART0_RTS{slash}GPIO07-Pad25)") (class "Default")
      (node (ref "U6") (pin "25") (pinfunction "UART0_RTS/GPIO07_25") (pintype "passive"))
    )
    (net (code "230") (name "unconnected-(U6-UART1_RX{slash}GPIO11-Pad31)") (class "Default")
      (node (ref "U6") (pin "31") (pinfunction "UART1_RX/GPIO11_31") (pintype "passive"))
    )
    (net (code "231") (name "unconnected-(U6-UART1_TX{slash}GPIO10-Pad30)") (class "Default")
      (node (ref "U6") (pin "30") (pinfunction "UART1_TX/GPIO10_30") (pintype "passive"))
    )
    (net (code "232") (name "unconnected-(U6-nReload{slash}GPIO03-Pad21)") (class "Default")
      (node (ref "U6") (pin "21") (pinfunction "nReload/GPIO03_21") (pintype "passive"))
    )
    (net (code "233") (name "unconnected-(U7-CLK-Pad6)") (class "Default")
      (node (ref "U7") (pin "6") (pinfunction "CLK_6") (pintype "passive+no_connect"))
    )
  )
)
